# SCH__Atlas_2026-06-26.net
KiCad netlist of a schematic drawn in EasyEDA
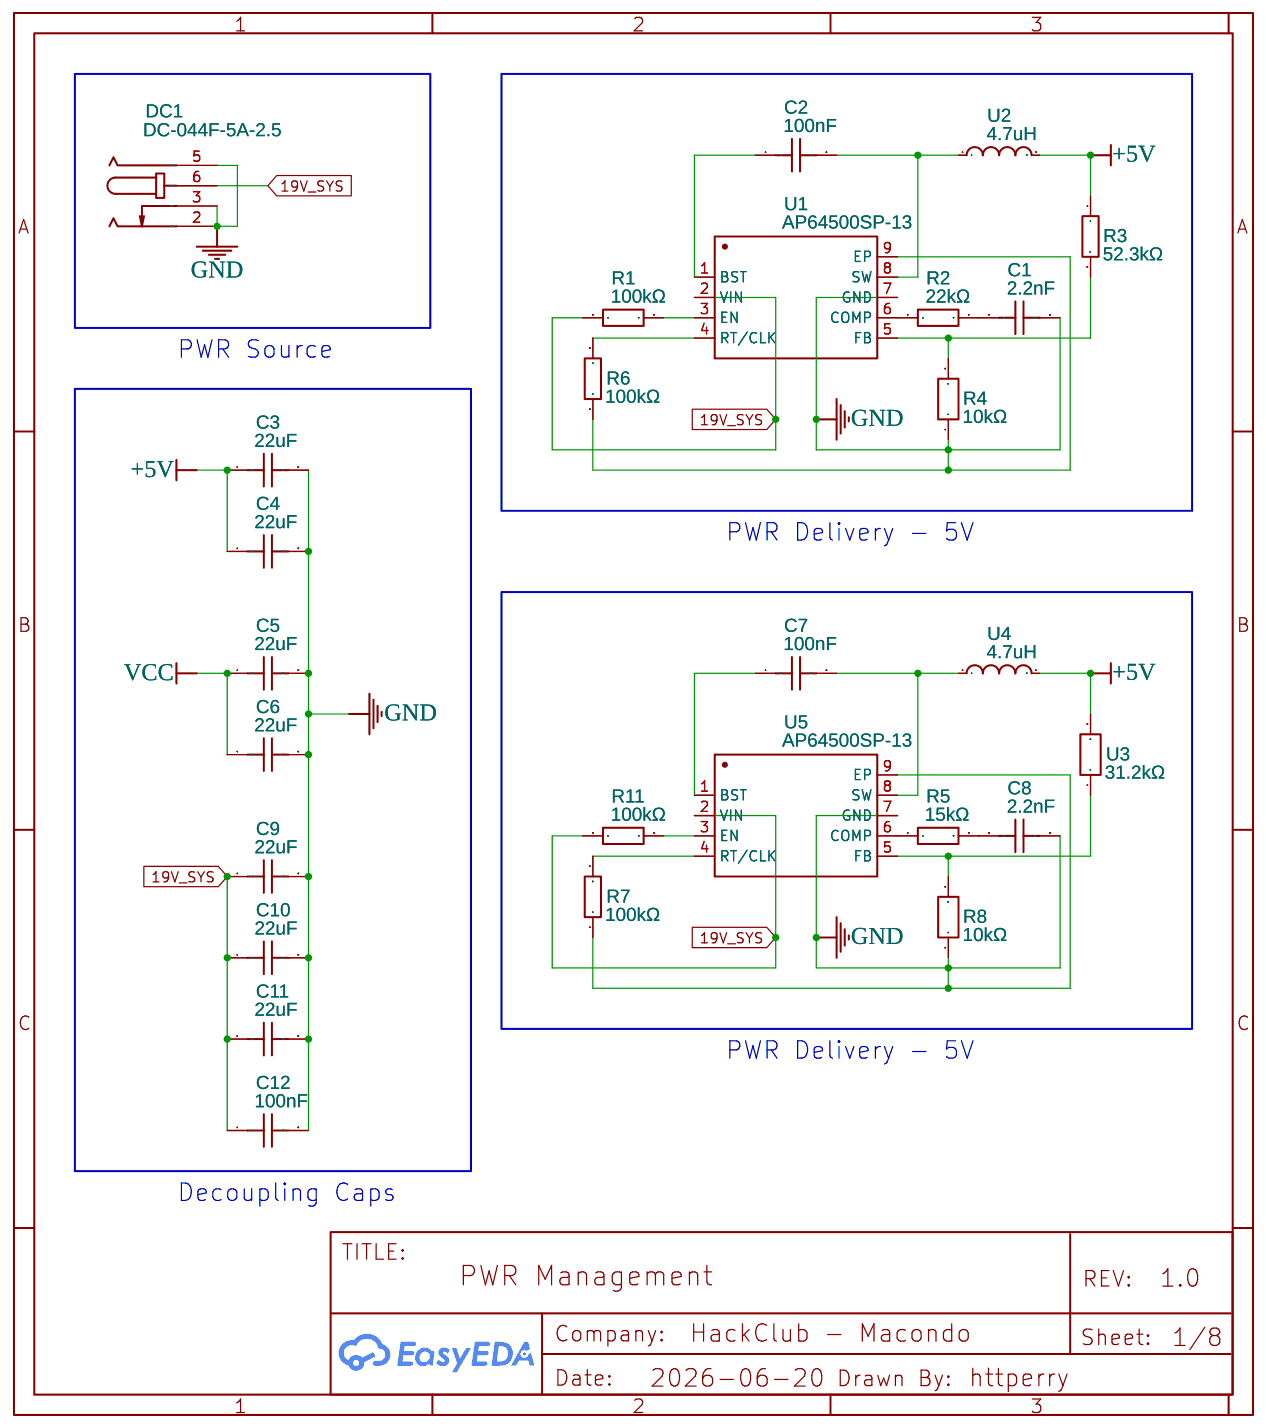
[diagram p0: PWR_Management]
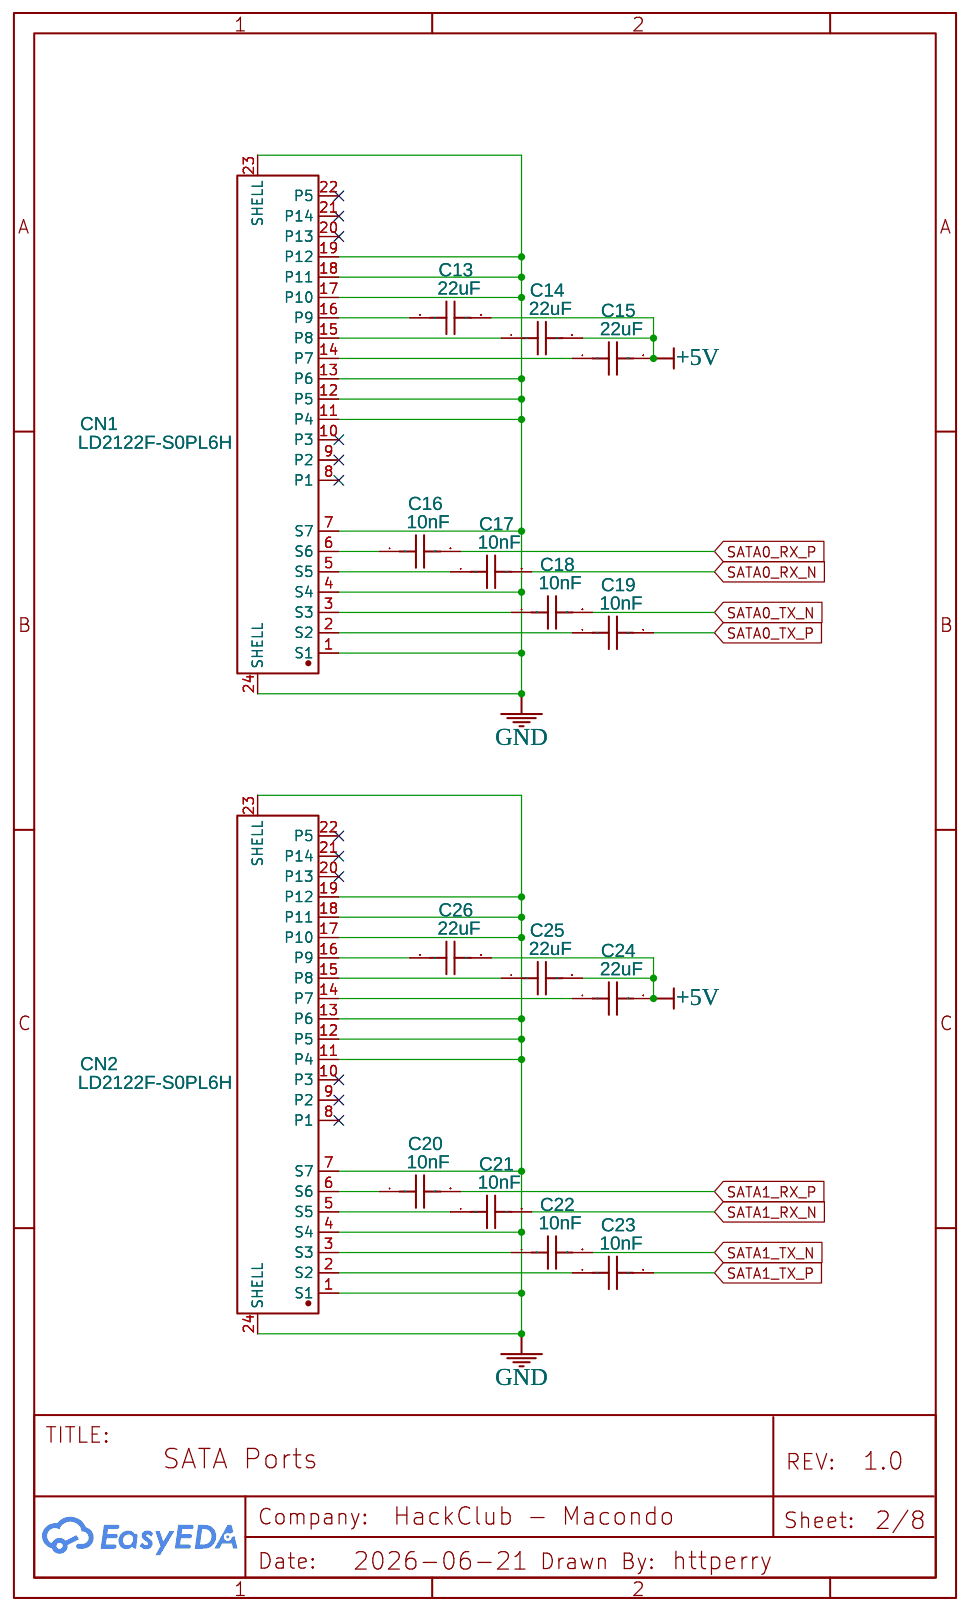
[diagram p1: SATA_Ports]
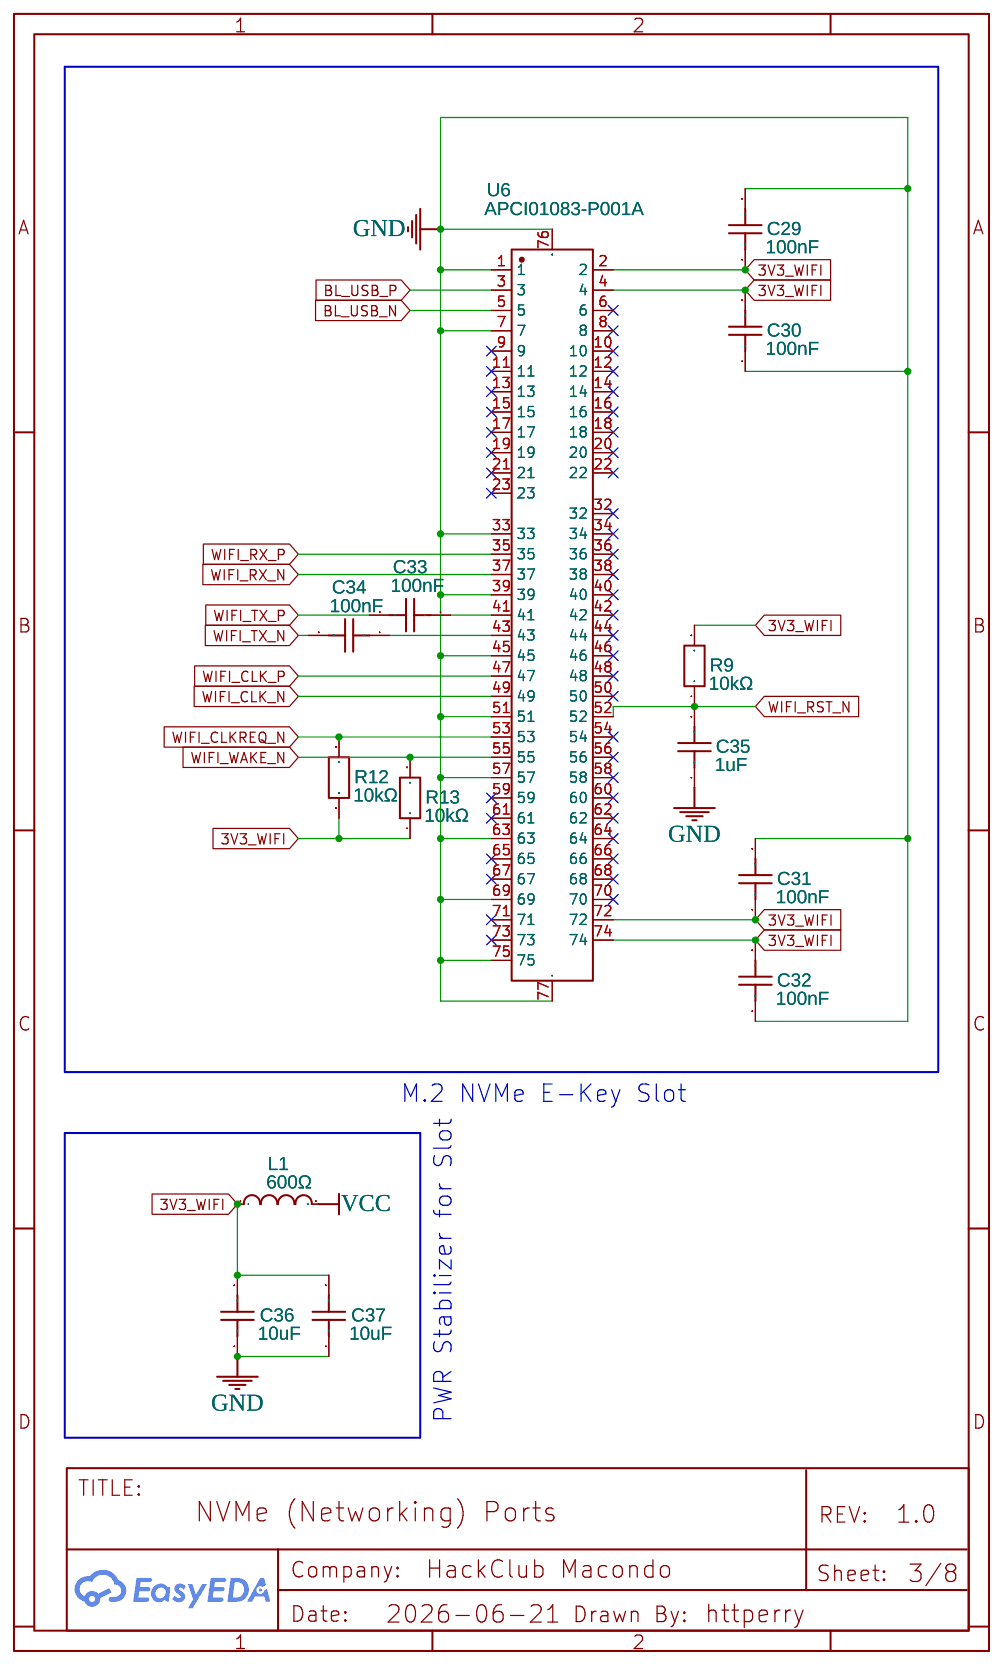
[diagram p2: NVMe_(Networking)_Ports]
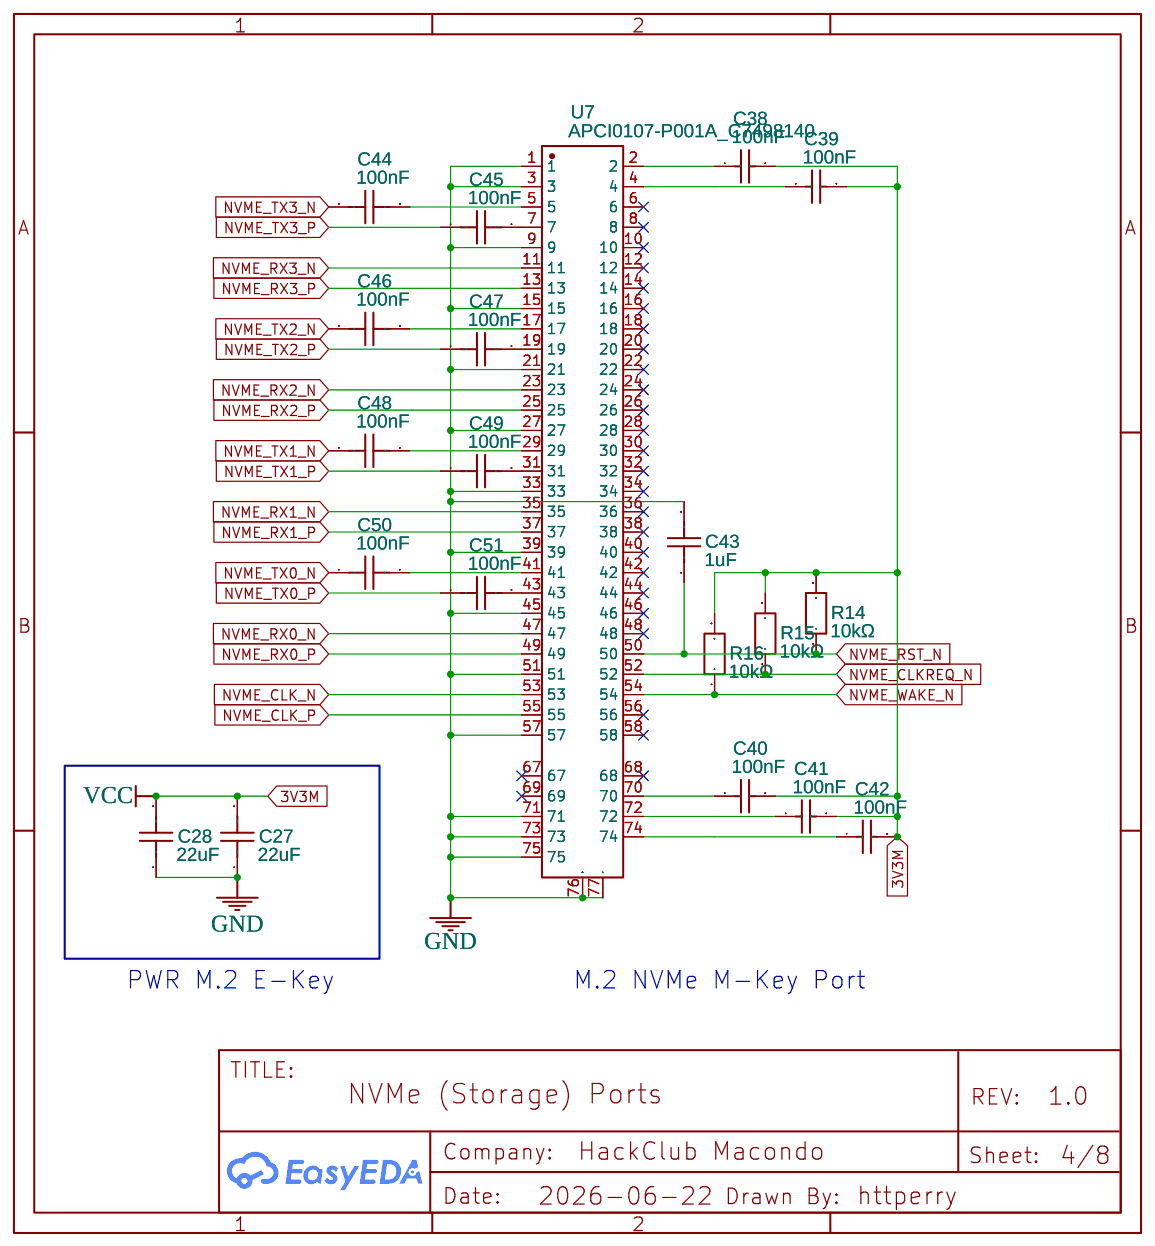
[diagram p3: NVMe_(Storage)_Ports]
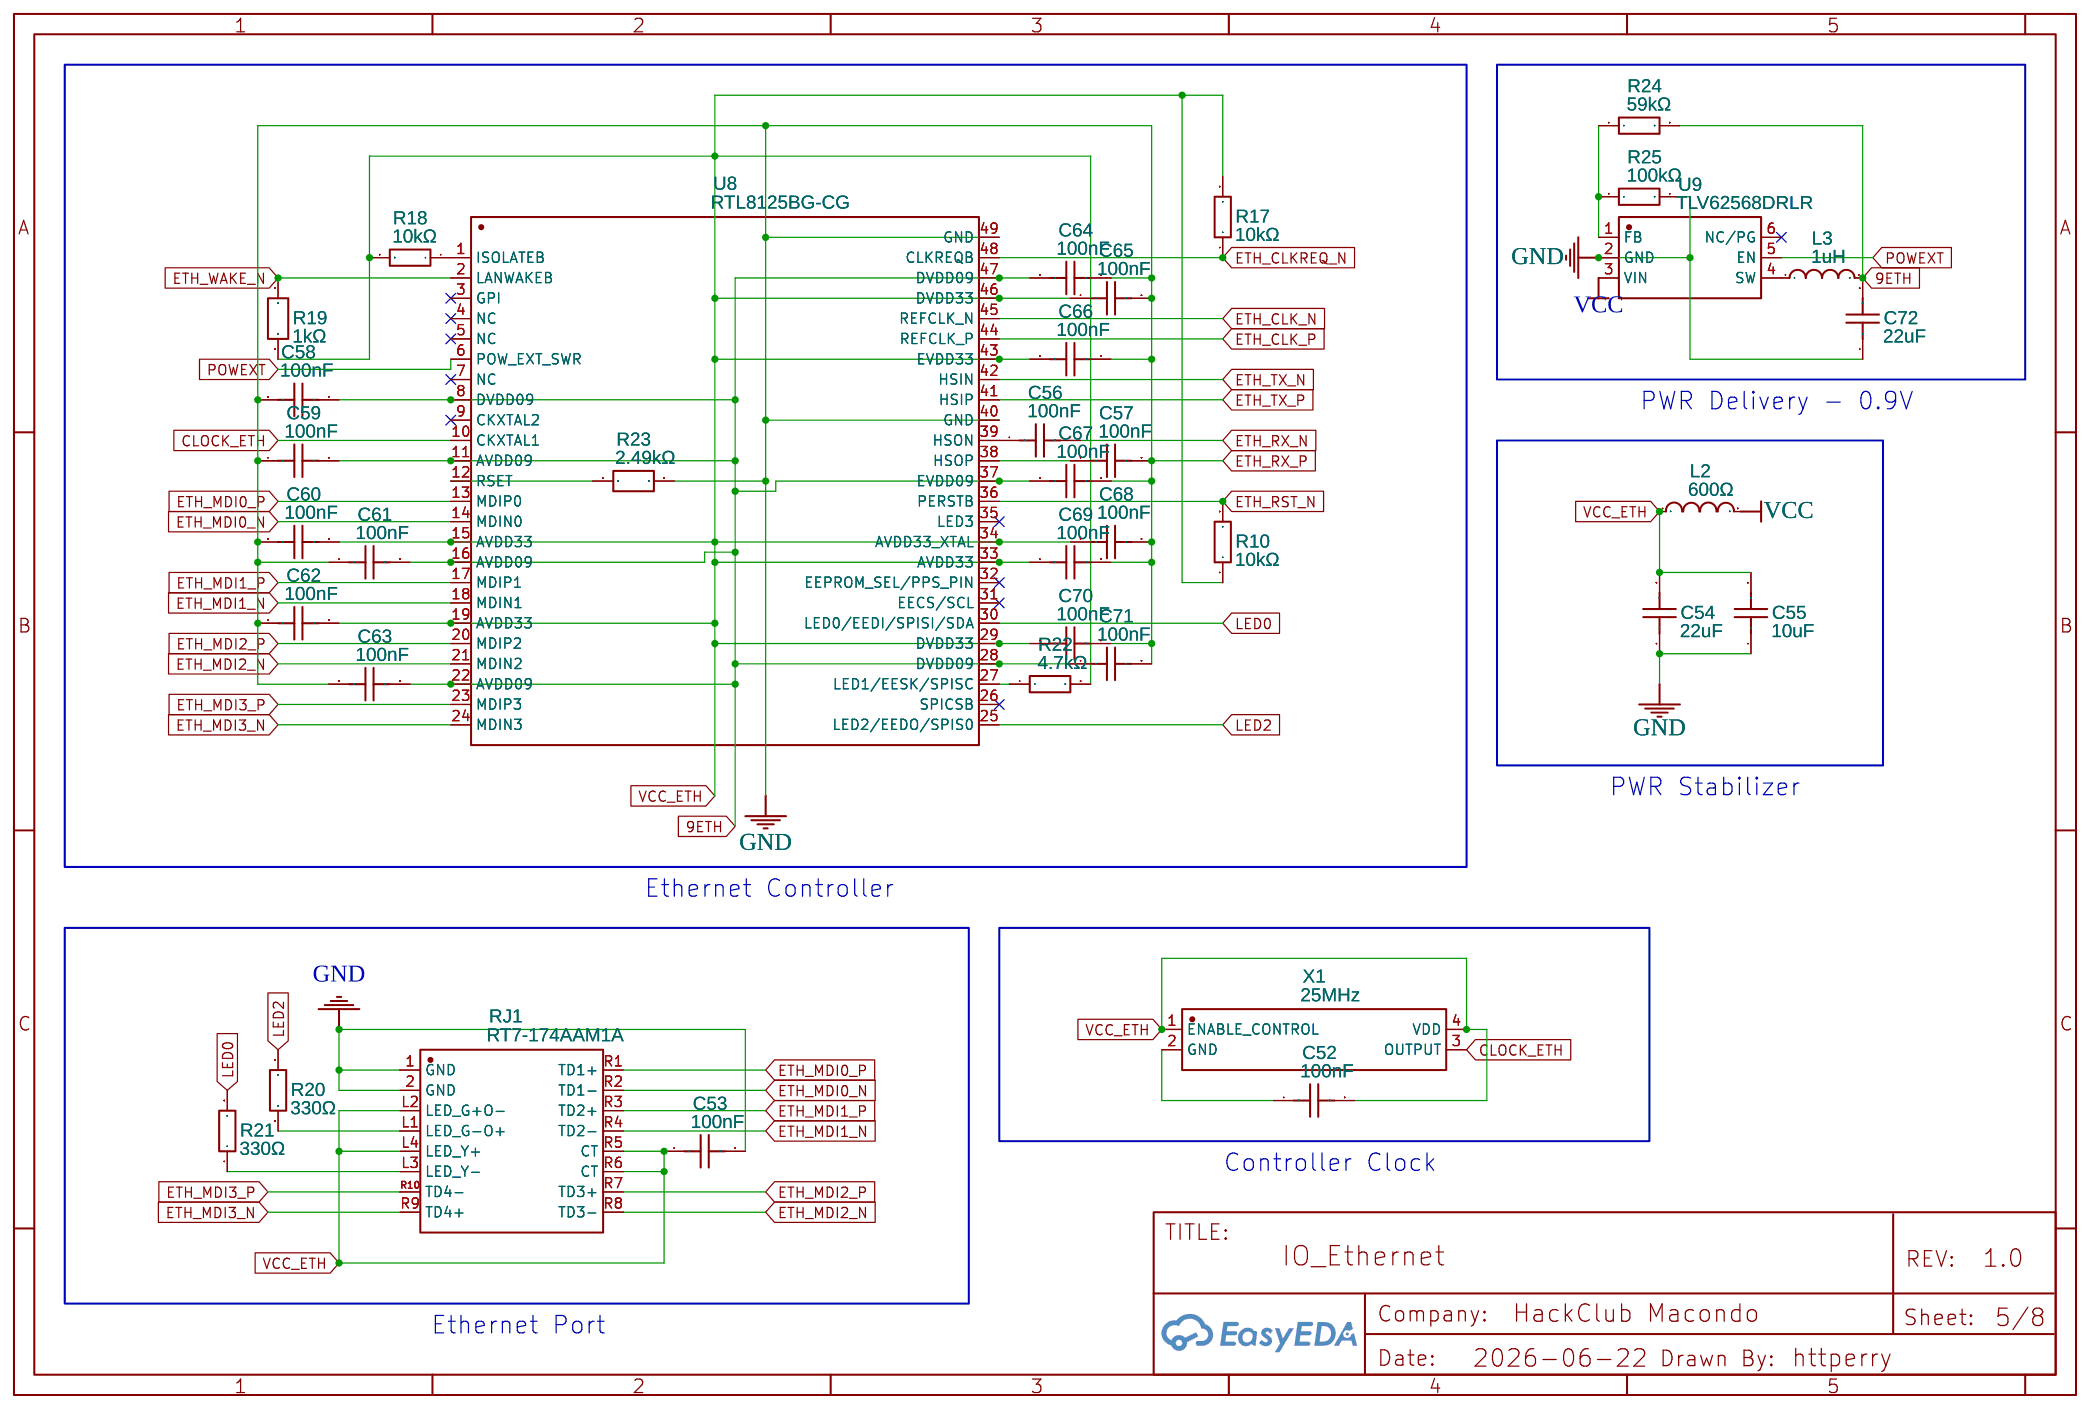
[diagram p4: IO_Ethernet]
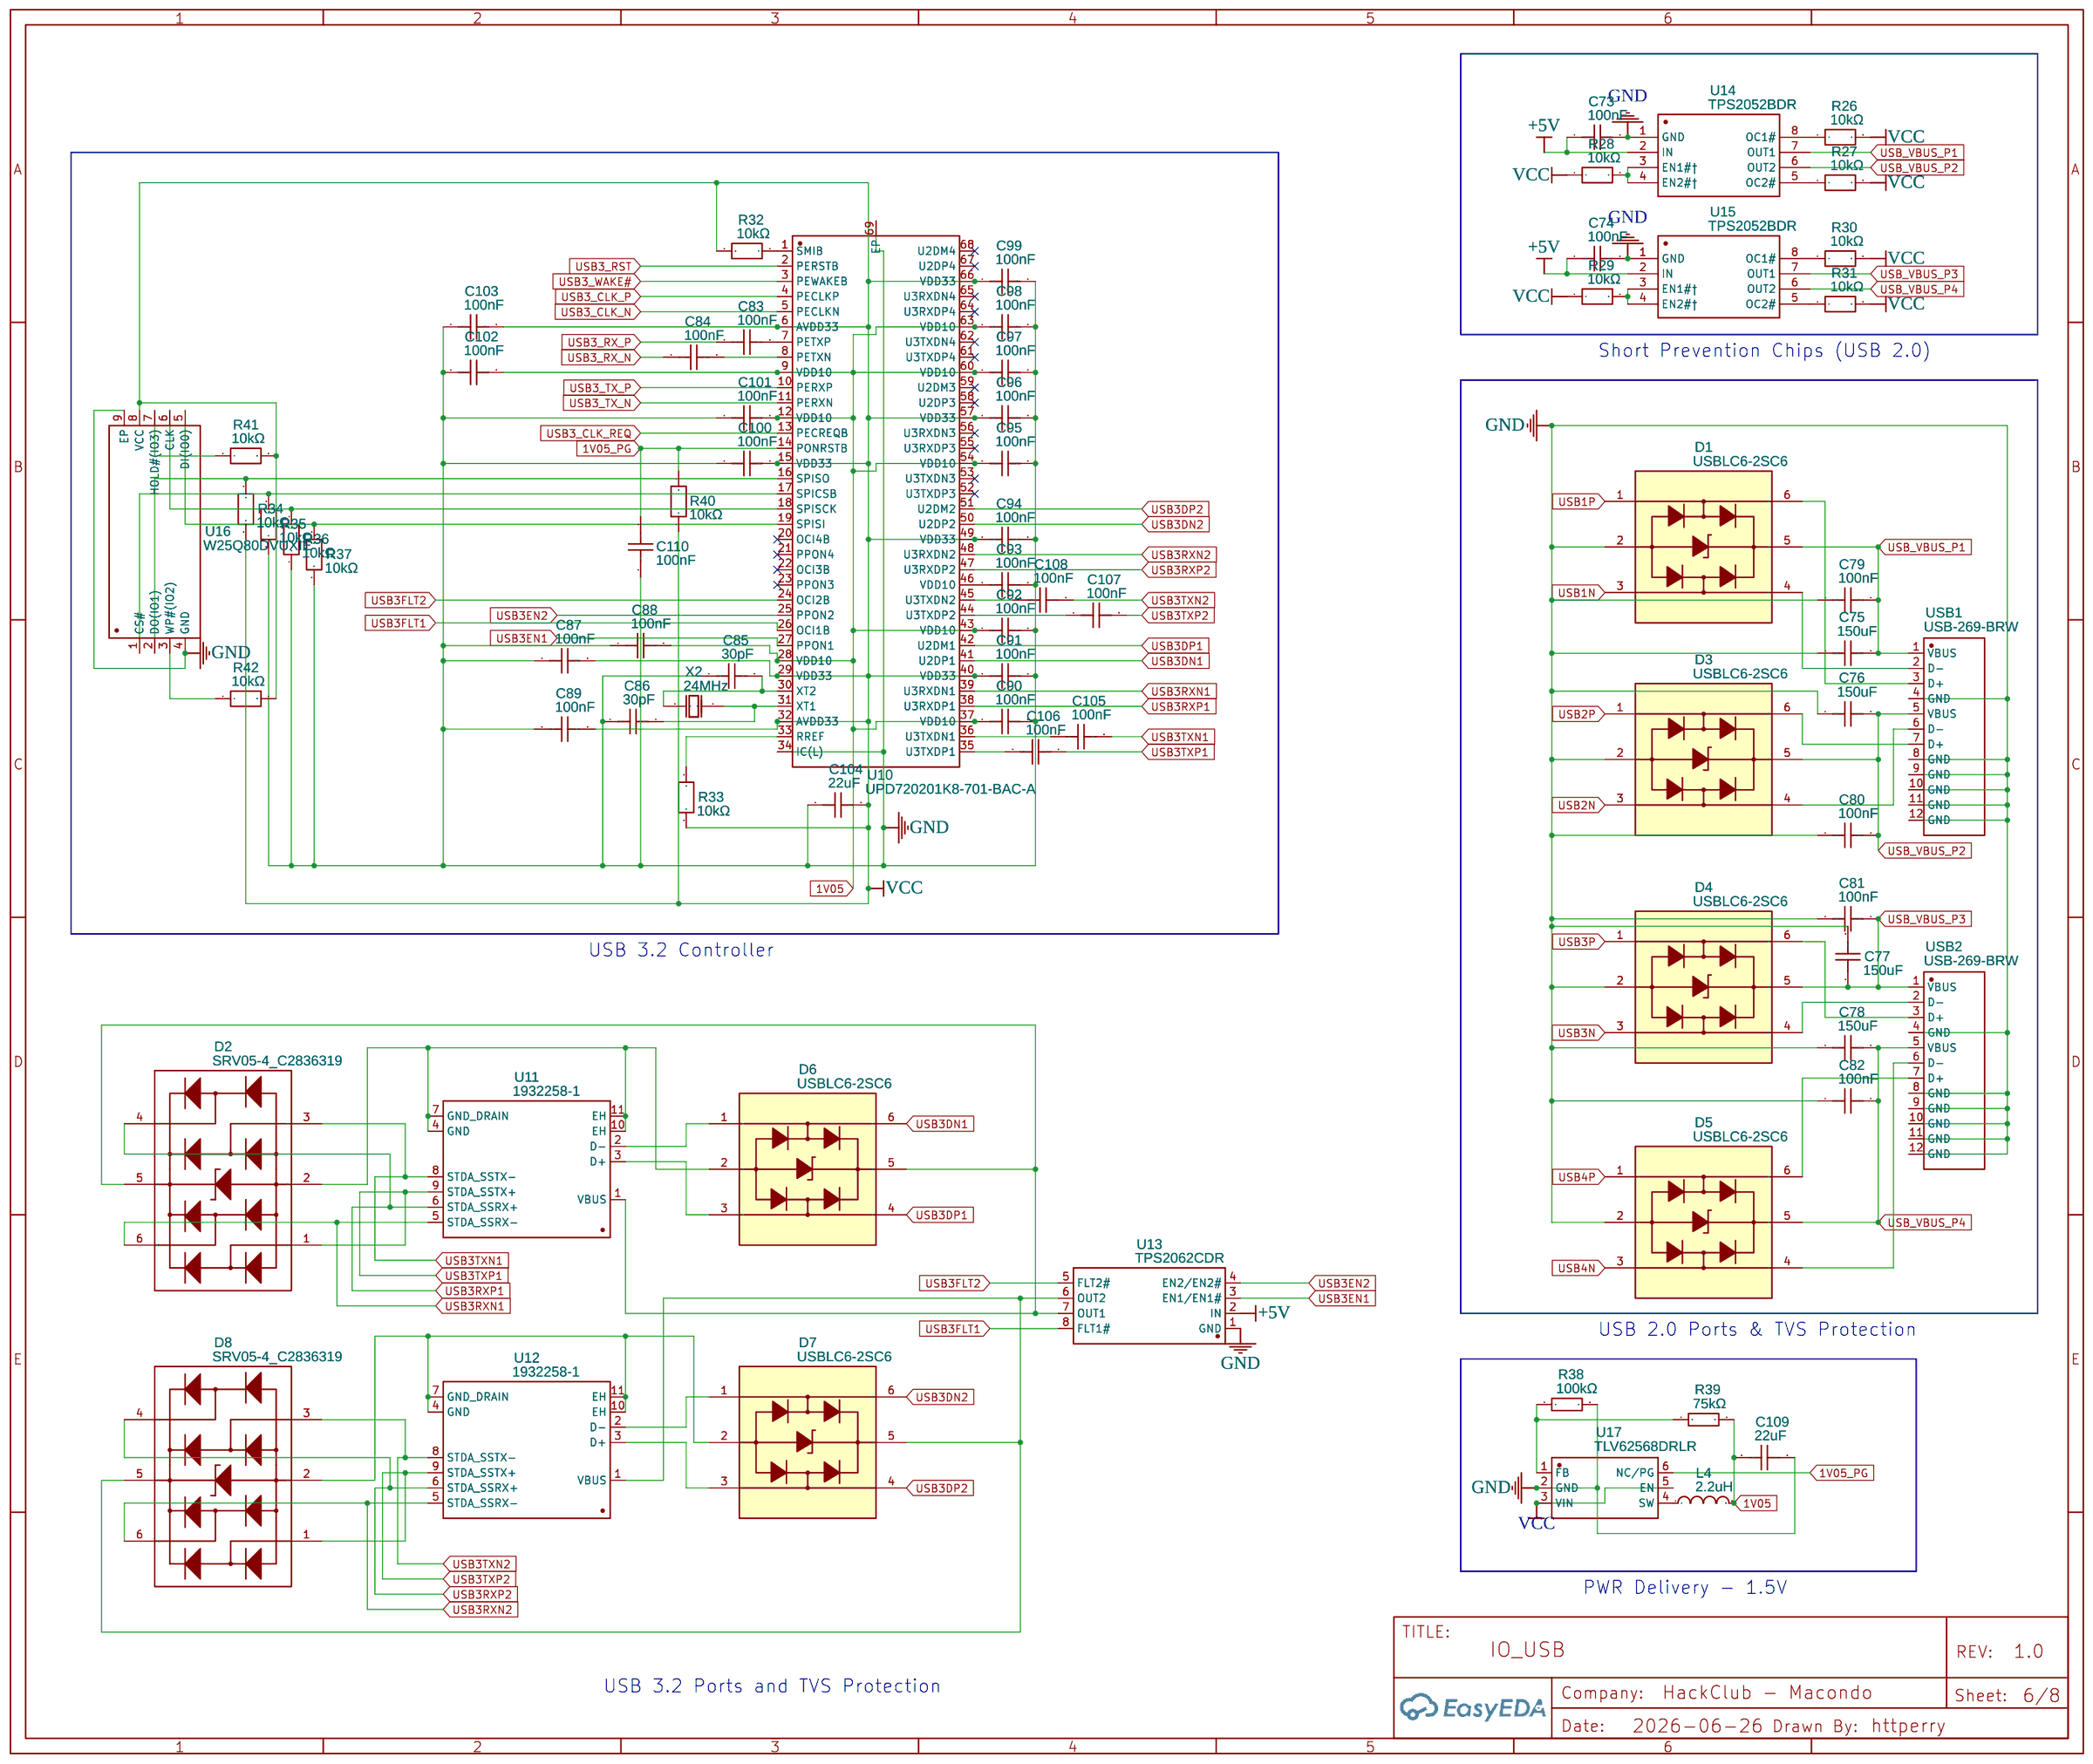
[diagram p5: IO_USB]

(export (version "E")
  (design (tool "Eeschema 10.0.6"))
  (components
    (comp (ref "C1")
      (value "2.2nF")
      (fields
        (field (name "Manufacturer Part") "FCC0603B222K500CT")
        (field (name "Manufacturer") "FOJAN(富捷)")
      )
      (libsource (lib "") (part "FCC0603B222K500CT"))
    )
    (comp (ref "C2")
      (value "100nF")
      (fields
        (field (name "Manufacturer Part") "GRM188R71H104KA93D")
        (field (name "Manufacturer") "muRata(村田)")
      )
      (libsource (lib "") (part "GRM188R71H104KA93D"))
    )
    (comp (ref "C3")
      (value "22uF")
      (fields
        (field (name "Manufacturer Part") "HGC0603R5226M160NTHJ")
        (field (name "Manufacturer") "Chinocera(华瓷)")
      )
      (libsource (lib "") (part "HGC0603R5226M160NTHJ"))
    )
    (comp (ref "C4")
      (value "22uF")
      (fields
        (field (name "Manufacturer Part") "HGC0603R5226M160NTHJ")
        (field (name "Manufacturer") "Chinocera(华瓷)")
      )
      (libsource (lib "") (part "HGC0603R5226M160NTHJ"))
    )
    (comp (ref "C5")
      (value "22uF")
      (fields
        (field (name "Manufacturer Part") "HGC0603R5226M160NTHJ")
        (field (name "Manufacturer") "Chinocera(华瓷)")
      )
      (libsource (lib "") (part "HGC0603R5226M160NTHJ"))
    )
    (comp (ref "C6")
      (value "22uF")
      (fields
        (field (name "Manufacturer Part") "HGC0603R5226M160NTHJ")
        (field (name "Manufacturer") "Chinocera(华瓷)")
      )
      (libsource (lib "") (part "HGC0603R5226M160NTHJ"))
    )
    (comp (ref "C7")
      (value "100nF")
      (fields
        (field (name "Manufacturer Part") "GRM188R71H104KA93D")
        (field (name "Manufacturer") "muRata(村田)")
      )
      (libsource (lib "") (part "GRM188R71H104KA93D"))
    )
    (comp (ref "C8")
      (value "2.2nF")
      (fields
        (field (name "Manufacturer Part") "FCC0603B222K500CT")
        (field (name "Manufacturer") "FOJAN(富捷)")
      )
      (libsource (lib "") (part "FCC0603B222K500CT"))
    )
    (comp (ref "C9")
      (value "22uF")
      (fields
        (field (name "Manufacturer Part") "KCM55QR71H226KH13K")
        (field (name "Manufacturer") "muRata(村田)")
      )
      (libsource (lib "") (part "KCM55QR71H226KH13K"))
    )
    (comp (ref "C10")
      (value "22uF")
      (fields
        (field (name "Manufacturer Part") "KCM55QR71H226KH13K")
        (field (name "Manufacturer") "muRata(村田)")
      )
      (libsource (lib "") (part "KCM55QR71H226KH13K"))
    )
    (comp (ref "C11")
      (value "22uF")
      (fields
        (field (name "Manufacturer Part") "KCM55QR71H226KH13K")
        (field (name "Manufacturer") "muRata(村田)")
      )
      (libsource (lib "") (part "KCM55QR71H226KH13K"))
    )
    (comp (ref "C12")
      (value "100nF")
      (fields
        (field (name "Manufacturer Part") "GRM188R71H104KA93D")
        (field (name "Manufacturer") "muRata(村田)")
      )
      (libsource (lib "") (part "GRM188R71H104KA93D"))
    )
    (comp (ref "DC1")
      (value "DC-044F-5A-2.5")
      (fields (field (name "Manufacturer") "XKB Connection(中国星坤)"))
      (libsource (lib "") (part "DC-044F-5A-2.5"))
    )
    (comp (ref "R1")
      (value "100kΩ")
      (fields (field (name "Manufacturer Part") "RS-03K1003FT") (field (name "Manufacturer") "FH(风华)"))
      (libsource (lib "") (part "RS-03K1003FT_C115320_1"))
    )
    (comp (ref "R2")
      (value "22kΩ")
      (fields (field (name "Manufacturer Part") "RS-03K2202FT") (field (name "Manufacturer") "FH(风华)"))
      (libsource (lib "") (part "RS-03K2202FT"))
    )
    (comp (ref "R3")
      (value "52.3kΩ")
      (fields (field (name "Manufacturer Part") "RS-03K5232FT") (field (name "Manufacturer") "FH(风华)"))
      (libsource (lib "") (part "RS-03K5232FT"))
    )
    (comp (ref "R4")
      (value "10kΩ")
      (fields (field (name "Manufacturer Part") "AR03BTS1002") (field (name "Manufacturer") "Viking(光颉)"))
      (libsource (lib "") (part "AR03BTS1002"))
    )
    (comp (ref "R5")
      (value "15kΩ")
      (fields (field (name "Manufacturer Part") "CR0603FA1502G") (field (name "Manufacturer") "LIZ(丽智电子)"))
      (libsource (lib "") (part "CR0603FA1502G"))
    )
    (comp (ref "R6")
      (value "100kΩ")
      (fields (field (name "Manufacturer Part") "RS-03K1003FT") (field (name "Manufacturer") "FH(风华)"))
      (libsource (lib "") (part "RS-03K1003FT_C115320"))
    )
    (comp (ref "R7")
      (value "100kΩ")
      (fields (field (name "Manufacturer Part") "RS-03K1003FT") (field (name "Manufacturer") "FH(风华)"))
      (libsource (lib "") (part "RS-03K1003FT_C115320"))
    )
    (comp (ref "R8")
      (value "10kΩ")
      (fields (field (name "Manufacturer Part") "AR03BTS1002") (field (name "Manufacturer") "Viking(光颉)"))
      (libsource (lib "") (part "AR03BTS1002"))
    )
    (comp (ref "R11")
      (value "100kΩ")
      (fields (field (name "Manufacturer Part") "RS-03K1003FT") (field (name "Manufacturer") "FH(风华)"))
      (libsource (lib "") (part "RS-03K1003FT_C115320_1"))
    )
    (comp (ref "U1")
      (value "AP64500SP-13")
      (fields (field (name "Manufacturer") "DIODES(美台)"))
      (libsource (lib "") (part "AP64500SP-13"))
    )
    (comp (ref "U2")
      (value "4.7uH")
      (fields (field (name "Manufacturer Part") "APH0630T4R7M") (field (name "Manufacturer") "APV(爱普微)"))
      (libsource (lib "") (part "APH0630T4R7M"))
    )
    (comp (ref "U3")
      (value "31.2kΩ")
      (fields (field (name "Manufacturer Part") "RT0603DRE0731K2L") (field (name "Manufacturer") "YAGEO(国巨)"))
      (libsource (lib "") (part "RT0603DRE0731K2L"))
    )
    (comp (ref "U4")
      (value "4.7uH")
      (fields (field (name "Manufacturer Part") "APH0630T4R7M") (field (name "Manufacturer") "APV(爱普微)"))
      (libsource (lib "") (part "APH0630T4R7M"))
    )
    (comp (ref "U5")
      (value "AP64500SP-13")
      (fields (field (name "Manufacturer") "DIODES(美台)"))
      (libsource (lib "") (part "AP64500SP-13"))
    )
    (comp (ref "C13")
      (value "22uF")
      (fields
        (field (name "Manufacturer Part") "HGC0603R5226M160NTHJ")
        (field (name "Manufacturer") "Chinocera(华瓷)")
      )
      (libsource (lib "") (part "HGC0603R5226M160NTHJ"))
    )
    (comp (ref "C14")
      (value "22uF")
      (fields
        (field (name "Manufacturer Part") "HGC0603R5226M160NTHJ")
        (field (name "Manufacturer") "Chinocera(华瓷)")
      )
      (libsource (lib "") (part "HGC0603R5226M160NTHJ"))
    )
    (comp (ref "C15")
      (value "22uF")
      (fields
        (field (name "Manufacturer Part") "HGC0603R5226M160NTHJ")
        (field (name "Manufacturer") "Chinocera(华瓷)")
      )
      (libsource (lib "") (part "HGC0603R5226M160NTHJ"))
    )
    (comp (ref "C16")
      (value "10nF")
      (fields
        (field (name "Manufacturer Part") "FCC0402B103K500AT")
        (field (name "Manufacturer") "FOJAN(富捷)")
      )
      (libsource (lib "") (part "FCC0402B103K500AT"))
    )
    (comp (ref "C17")
      (value "10nF")
      (fields
        (field (name "Manufacturer Part") "FCC0402B103K500AT")
        (field (name "Manufacturer") "FOJAN(富捷)")
      )
      (libsource (lib "") (part "FCC0402B103K500AT"))
    )
    (comp (ref "C18")
      (value "10nF")
      (fields
        (field (name "Manufacturer Part") "FCC0402B103K500AT")
        (field (name "Manufacturer") "FOJAN(富捷)")
      )
      (libsource (lib "") (part "FCC0402B103K500AT"))
    )
    (comp (ref "C19")
      (value "10nF")
      (fields
        (field (name "Manufacturer Part") "FCC0402B103K500AT")
        (field (name "Manufacturer") "FOJAN(富捷)")
      )
      (libsource (lib "") (part "FCC0402B103K500AT"))
    )
    (comp (ref "C20")
      (value "10nF")
      (fields
        (field (name "Manufacturer Part") "FCC0402B103K500AT")
        (field (name "Manufacturer") "FOJAN(富捷)")
      )
      (libsource (lib "") (part "FCC0402B103K500AT"))
    )
    (comp (ref "C21")
      (value "10nF")
      (fields
        (field (name "Manufacturer Part") "FCC0402B103K500AT")
        (field (name "Manufacturer") "FOJAN(富捷)")
      )
      (libsource (lib "") (part "FCC0402B103K500AT"))
    )
    (comp (ref "C22")
      (value "10nF")
      (fields
        (field (name "Manufacturer Part") "FCC0402B103K500AT")
        (field (name "Manufacturer") "FOJAN(富捷)")
      )
      (libsource (lib "") (part "FCC0402B103K500AT"))
    )
    (comp (ref "C23")
      (value "10nF")
      (fields
        (field (name "Manufacturer Part") "FCC0402B103K500AT")
        (field (name "Manufacturer") "FOJAN(富捷)")
      )
      (libsource (lib "") (part "FCC0402B103K500AT"))
    )
    (comp (ref "C24")
      (value "22uF")
      (fields
        (field (name "Manufacturer Part") "HGC0603R5226M160NTHJ")
        (field (name "Manufacturer") "Chinocera(华瓷)")
      )
      (libsource (lib "") (part "HGC0603R5226M160NTHJ"))
    )
    (comp (ref "C25")
      (value "22uF")
      (fields
        (field (name "Manufacturer Part") "HGC0603R5226M160NTHJ")
        (field (name "Manufacturer") "Chinocera(华瓷)")
      )
      (libsource (lib "") (part "HGC0603R5226M160NTHJ"))
    )
    (comp (ref "C26")
      (value "22uF")
      (fields
        (field (name "Manufacturer Part") "HGC0603R5226M160NTHJ")
        (field (name "Manufacturer") "Chinocera(华瓷)")
      )
      (libsource (lib "") (part "HGC0603R5226M160NTHJ"))
    )
    (comp (ref "CN1")
      (value "LD2122F-S0PL6H")
      (fields (field (name "Manufacturer") "FOXCONN(富士康)"))
      (libsource (lib "") (part "LD2122F-S0PL6H"))
    )
    (comp (ref "CN2")
      (value "LD2122F-S0PL6H")
      (fields (field (name "Manufacturer") "FOXCONN(富士康)"))
      (libsource (lib "") (part "LD2122F-S0PL6H"))
    )
    (comp (ref "C29")
      (value "100nF")
      (fields
        (field (name "Manufacturer Part") "CC0402KRX5R6BB104")
        (field (name "Manufacturer") "YAGEO(国巨)")
      )
      (libsource (lib "") (part "CC0402KRX5R6BB104_1"))
    )
    (comp (ref "C30")
      (value "100nF")
      (fields
        (field (name "Manufacturer Part") "CC0402KRX5R6BB104")
        (field (name "Manufacturer") "YAGEO(国巨)")
      )
      (libsource (lib "") (part "CC0402KRX5R6BB104_1"))
    )
    (comp (ref "C31")
      (value "100nF")
      (fields
        (field (name "Manufacturer Part") "CC0402KRX5R6BB104")
        (field (name "Manufacturer") "YAGEO(国巨)")
      )
      (libsource (lib "") (part "CC0402KRX5R6BB104_1"))
    )
    (comp (ref "C32")
      (value "100nF")
      (fields
        (field (name "Manufacturer Part") "CC0402KRX5R6BB104")
        (field (name "Manufacturer") "YAGEO(国巨)")
      )
      (libsource (lib "") (part "CC0402KRX5R6BB104_1"))
    )
    (comp (ref "C33")
      (value "100nF")
      (fields
        (field (name "Manufacturer Part") "CC0402KRX5R6BB104")
        (field (name "Manufacturer") "YAGEO(国巨)")
      )
      (libsource (lib "") (part "CC0402KRX5R6BB104"))
    )
    (comp (ref "C34")
      (value "100nF")
      (fields
        (field (name "Manufacturer Part") "CC0402KRX5R6BB104")
        (field (name "Manufacturer") "YAGEO(国巨)")
      )
      (libsource (lib "") (part "CC0402KRX5R6BB104"))
    )
    (comp (ref "C35")
      (value "1uF")
      (fields
        (field (name "Manufacturer Part") "TCC0402X5R105K160AT")
        (field (name "Manufacturer") "CCTC(三环)")
      )
      (libsource (lib "") (part "TCC0402X5R105K160AT"))
    )
    (comp (ref "C36")
      (value "10uF")
      (fields
        (field (name "Manufacturer Part") "CGA0805X5R106K500MT")
        (field (name "Manufacturer") "HRE(芯声)")
      )
      (libsource (lib "") (part "CGA0805X5R106K500MT"))
    )
    (comp (ref "C37")
      (value "10uF")
      (fields
        (field (name "Manufacturer Part") "CGA0805X5R106K500MT")
        (field (name "Manufacturer") "HRE(芯声)")
      )
      (libsource (lib "") (part "CGA0805X5R106K500MT"))
    )
    (comp (ref "L1")
      (value "600Ω")
      (fields (field (name "Manufacturer Part") "MPZ2012S601AT000") (field (name "Manufacturer") "TDK"))
      (libsource (lib "") (part "MPZ2012S601AT000"))
    )
    (comp (ref "R9")
      (value "10kΩ")
      (fields (field (name "Manufacturer Part") "FRC0402F1002TS") (field (name "Manufacturer") "FOJAN(富捷)"))
      (libsource (lib "") (part "FRC0402F1002TS"))
    )
    (comp (ref "R12")
      (value "10kΩ")
      (fields (field (name "Manufacturer Part") "FRC0402F1002TS") (field (name "Manufacturer") "FOJAN(富捷)"))
      (libsource (lib "") (part "FRC0402F1002TS"))
    )
    (comp (ref "R13")
      (value "10kΩ")
      (fields (field (name "Manufacturer Part") "FRC0402F1002TS") (field (name "Manufacturer") "FOJAN(富捷)"))
      (libsource (lib "") (part "FRC0402F1002TS"))
    )
    (comp (ref "U6")
      (value "APCI01083-P001A")
      (fields (field (name "Manufacturer") "LX(连欣科技)"))
      (libsource (lib "") (part "APCI01083-P001A"))
    )
    (comp (ref "C27")
      (value "22uF")
      (fields
        (field (name "Manufacturer Part") "CL21A226MAYNNNE")
        (field (name "Manufacturer") "SAMSUNG(三星)")
      )
      (libsource (lib "") (part "CL21A226MAYNNNE"))
    )
    (comp (ref "C28")
      (value "22uF")
      (fields
        (field (name "Manufacturer Part") "CL21A226MAYNNNE")
        (field (name "Manufacturer") "SAMSUNG(三星)")
      )
      (libsource (lib "") (part "CL21A226MAYNNNE"))
    )
    (comp (ref "C38")
      (value "100nF")
      (fields
        (field (name "Manufacturer Part") "CC0402KRX5R8BB104")
        (field (name "Manufacturer") "YAGEO(国巨)")
      )
      (libsource (lib "") (part "CC0402KRX5R8BB104"))
    )
    (comp (ref "C39")
      (value "100nF")
      (fields
        (field (name "Manufacturer Part") "CC0402KRX5R8BB104")
        (field (name "Manufacturer") "YAGEO(国巨)")
      )
      (libsource (lib "") (part "CC0402KRX5R8BB104"))
    )
    (comp (ref "C40")
      (value "100nF")
      (fields
        (field (name "Manufacturer Part") "CC0402KRX5R8BB104")
        (field (name "Manufacturer") "YAGEO(国巨)")
      )
      (libsource (lib "") (part "CC0402KRX5R8BB104"))
    )
    (comp (ref "C41")
      (value "100nF")
      (fields
        (field (name "Manufacturer Part") "CC0402KRX5R8BB104")
        (field (name "Manufacturer") "YAGEO(国巨)")
      )
      (libsource (lib "") (part "CC0402KRX5R8BB104"))
    )
    (comp (ref "C42")
      (value "100nF")
      (fields
        (field (name "Manufacturer Part") "CC0402KRX5R8BB104")
        (field (name "Manufacturer") "YAGEO(国巨)")
      )
      (libsource (lib "") (part "CC0402KRX5R8BB104"))
    )
    (comp (ref "C43")
      (value "1uF")
      (fields
        (field (name "Manufacturer Part") "HGC0402R5105K500NTEJ")
        (field (name "Manufacturer") "Chinocera(华瓷)")
      )
      (libsource (lib "") (part "HGC0402R5105K500NTEJ"))
    )
    (comp (ref "C44")
      (value "100nF")
      (fields
        (field (name "Manufacturer Part") "GRM155R71H104KE14J")
        (field (name "Manufacturer") "muRata(村田)")
      )
      (libsource (lib "") (part "GRM155R71H104KE14J"))
    )
    (comp (ref "C45")
      (value "100nF")
      (fields
        (field (name "Manufacturer Part") "GRM155R71H104KE14J")
        (field (name "Manufacturer") "muRata(村田)")
      )
      (libsource (lib "") (part "GRM155R71H104KE14J"))
    )
    (comp (ref "C46")
      (value "100nF")
      (fields
        (field (name "Manufacturer Part") "GRM155R71H104KE14J")
        (field (name "Manufacturer") "muRata(村田)")
      )
      (libsource (lib "") (part "GRM155R71H104KE14J"))
    )
    (comp (ref "C47")
      (value "100nF")
      (fields
        (field (name "Manufacturer Part") "GRM155R71H104KE14J")
        (field (name "Manufacturer") "muRata(村田)")
      )
      (libsource (lib "") (part "GRM155R71H104KE14J"))
    )
    (comp (ref "C48")
      (value "100nF")
      (fields
        (field (name "Manufacturer Part") "GRM155R71H104KE14J")
        (field (name "Manufacturer") "muRata(村田)")
      )
      (libsource (lib "") (part "GRM155R71H104KE14J"))
    )
    (comp (ref "C49")
      (value "100nF")
      (fields
        (field (name "Manufacturer Part") "GRM155R71H104KE14J")
        (field (name "Manufacturer") "muRata(村田)")
      )
      (libsource (lib "") (part "GRM155R71H104KE14J"))
    )
    (comp (ref "C50")
      (value "100nF")
      (fields
        (field (name "Manufacturer Part") "GRM155R71H104KE14J")
        (field (name "Manufacturer") "muRata(村田)")
      )
      (libsource (lib "") (part "GRM155R71H104KE14J"))
    )
    (comp (ref "C51")
      (value "100nF")
      (fields
        (field (name "Manufacturer Part") "GRM155R71H104KE14J")
        (field (name "Manufacturer") "muRata(村田)")
      )
      (libsource (lib "") (part "GRM155R71H104KE14J"))
    )
    (comp (ref "R14")
      (value "10kΩ")
      (fields (field (name "Manufacturer Part") "FRC0402F1002TS") (field (name "Manufacturer") "FOJAN(富捷)"))
      (libsource (lib "") (part "FRC0402F1002TS"))
    )
    (comp (ref "R15")
      (value "10kΩ")
      (fields (field (name "Manufacturer Part") "FRC0402F1002TS") (field (name "Manufacturer") "FOJAN(富捷)"))
      (libsource (lib "") (part "FRC0402F1002TS"))
    )
    (comp (ref "R16")
      (value "10kΩ")
      (fields (field (name "Manufacturer Part") "FRC0402F1002TS") (field (name "Manufacturer") "FOJAN(富捷)"))
      (libsource (lib "") (part "FRC0402F1002TS"))
    )
    (comp (ref "U7")
      (value "APCI0107-P001A_C7498140")
      (fields (field (name "Manufacturer Part") "APCI0107-P001A") (field (name "Manufacturer") "LX(连欣科技)"))
      (libsource (lib "") (part "APCI0107-P001A_C7498140"))
    )
    (comp (ref "C52")
      (value "100nF")
      (fields
        (field (name "Manufacturer Part") "GRM155R71H104KE14J")
        (field (name "Manufacturer") "muRata(村田)")
      )
      (libsource (lib "") (part "GRM155R71H104KE14J"))
    )
    (comp (ref "C53")
      (value "100nF")
      (fields
        (field (name "Manufacturer Part") "GRM155R71H104KE14J")
        (field (name "Manufacturer") "muRata(村田)")
      )
      (libsource (lib "") (part "GRM155R71H104KE14J"))
    )
    (comp (ref "C54")
      (value "22uF")
      (fields
        (field (name "Manufacturer Part") "GRT21BR61E226ME13L")
        (field (name "Manufacturer") "muRata(村田)")
      )
      (libsource (lib "") (part "GRT21BR61E226ME13L"))
    )
    (comp (ref "C55")
      (value "10uF")
      (fields
        (field (name "Manufacturer Part") "TCC0805X5R106K250FT")
        (field (name "Manufacturer") "CCTC(三环)")
      )
      (libsource (lib "") (part "TCC0805X5R106K250FT"))
    )
    (comp (ref "C56")
      (value "100nF")
      (fields
        (field (name "Manufacturer Part") "GRM155R71H104KE14J")
        (field (name "Manufacturer") "muRata(村田)")
      )
      (libsource (lib "") (part "GRM155R71H104KE14J"))
    )
    (comp (ref "C57")
      (value "100nF")
      (fields
        (field (name "Manufacturer Part") "GRM155R71H104KE14J")
        (field (name "Manufacturer") "muRata(村田)")
      )
      (libsource (lib "") (part "GRM155R71H104KE14J"))
    )
    (comp (ref "C58")
      (value "100nF")
      (fields
        (field (name "Manufacturer Part") "GRM155R71H104KE14J")
        (field (name "Manufacturer") "muRata(村田)")
      )
      (libsource (lib "") (part "GRM155R71H104KE14J_1"))
    )
    (comp (ref "C59")
      (value "100nF")
      (fields
        (field (name "Manufacturer Part") "GRM155R71H104KE14J")
        (field (name "Manufacturer") "muRata(村田)")
      )
      (libsource (lib "") (part "GRM155R71H104KE14J"))
    )
    (comp (ref "C60")
      (value "100nF")
      (fields
        (field (name "Manufacturer Part") "GRM155R71H104KE14J")
        (field (name "Manufacturer") "muRata(村田)")
      )
      (libsource (lib "") (part "GRM155R71H104KE14J"))
    )
    (comp (ref "C61")
      (value "100nF")
      (fields
        (field (name "Manufacturer Part") "GRM155R71H104KE14J")
        (field (name "Manufacturer") "muRata(村田)")
      )
      (libsource (lib "") (part "GRM155R71H104KE14J"))
    )
    (comp (ref "C62")
      (value "100nF")
      (fields
        (field (name "Manufacturer Part") "GRM155R71H104KE14J")
        (field (name "Manufacturer") "muRata(村田)")
      )
      (libsource (lib "") (part "GRM155R71H104KE14J"))
    )
    (comp (ref "C63")
      (value "100nF")
      (fields
        (field (name "Manufacturer Part") "GRM155R71H104KE14J")
        (field (name "Manufacturer") "muRata(村田)")
      )
      (libsource (lib "") (part "GRM155R71H104KE14J"))
    )
    (comp (ref "C64")
      (value "100nF")
      (fields
        (field (name "Manufacturer Part") "GRM155R71H104KE14J")
        (field (name "Manufacturer") "muRata(村田)")
      )
      (libsource (lib "") (part "GRM155R71H104KE14J"))
    )
    (comp (ref "C65")
      (value "100nF")
      (fields
        (field (name "Manufacturer Part") "GRM155R71H104KE14J")
        (field (name "Manufacturer") "muRata(村田)")
      )
      (libsource (lib "") (part "GRM155R71H104KE14J"))
    )
    (comp (ref "C66")
      (value "100nF")
      (fields
        (field (name "Manufacturer Part") "GRM155R71H104KE14J")
        (field (name "Manufacturer") "muRata(村田)")
      )
      (libsource (lib "") (part "GRM155R71H104KE14J"))
    )
    (comp (ref "C67")
      (value "100nF")
      (fields
        (field (name "Manufacturer Part") "GRM155R71H104KE14J")
        (field (name "Manufacturer") "muRata(村田)")
      )
      (libsource (lib "") (part "GRM155R71H104KE14J"))
    )
    (comp (ref "C68")
      (value "100nF")
      (fields
        (field (name "Manufacturer Part") "GRM155R71H104KE14J")
        (field (name "Manufacturer") "muRata(村田)")
      )
      (libsource (lib "") (part "GRM155R71H104KE14J"))
    )
    (comp (ref "C69")
      (value "100nF")
      (fields
        (field (name "Manufacturer Part") "GRM155R71H104KE14J")
        (field (name "Manufacturer") "muRata(村田)")
      )
      (libsource (lib "") (part "GRM155R71H104KE14J"))
    )
    (comp (ref "C70")
      (value "100nF")
      (fields
        (field (name "Manufacturer Part") "GRM155R71H104KE14J")
        (field (name "Manufacturer") "muRata(村田)")
      )
      (libsource (lib "") (part "GRM155R71H104KE14J"))
    )
    (comp (ref "C71")
      (value "100nF")
      (fields
        (field (name "Manufacturer Part") "GRM155R71H104KE14J")
        (field (name "Manufacturer") "muRata(村田)")
      )
      (libsource (lib "") (part "GRM155R71H104KE14J"))
    )
    (comp (ref "C72")
      (value "22uF")
      (fields
        (field (name "Manufacturer Part") "GRT21BR61E226ME13L")
        (field (name "Manufacturer") "muRata(村田)")
      )
      (libsource (lib "") (part "GRT21BR61E226ME13L"))
    )
    (comp (ref "L2")
      (value "600Ω")
      (fields (field (name "Manufacturer Part") "MPZ2012S601AT000") (field (name "Manufacturer") "TDK"))
      (libsource (lib "") (part "MPZ2012S601AT000"))
    )
    (comp (ref "L3")
      (value "1uH")
      (fields (field (name "Manufacturer Part") "XRIM201612S1R0MBCA") (field (name "Manufacturer") "XR(祥如)"))
      (libsource (lib "") (part "XRIM201612S1R0MBCA"))
    )
    (comp (ref "R10")
      (value "10kΩ")
      (fields (field (name "Manufacturer Part") "ERA2AEB103X") (field (name "Manufacturer") "PANASONIC(松下)"))
      (libsource (lib "") (part "ERA2AEB103X"))
    )
    (comp (ref "R17")
      (value "10kΩ")
      (fields (field (name "Manufacturer Part") "ERA2AEB103X") (field (name "Manufacturer") "PANASONIC(松下)"))
      (libsource (lib "") (part "ERA2AEB103X"))
    )
    (comp (ref "R18")
      (value "10kΩ")
      (fields (field (name "Manufacturer Part") "ERA2AEB103X") (field (name "Manufacturer") "PANASONIC(松下)"))
      (libsource (lib "") (part "ERA2AEB103X_1"))
    )
    (comp (ref "R19")
      (value "1kΩ")
      (fields (field (name "Manufacturer Part") "RT0402BRD071KL") (field (name "Manufacturer") "YAGEO(国巨)"))
      (libsource (lib "") (part "RT0402BRD071KL"))
    )
    (comp (ref "R20")
      (value "330Ω")
      (fields (field (name "Manufacturer Part") "RC0402JR-07330RL") (field (name "Manufacturer") "YAGEO(国巨)"))
      (libsource (lib "") (part "RC0402JR-07330RL_1"))
    )
    (comp (ref "R21")
      (value "330Ω")
      (fields (field (name "Manufacturer Part") "RC0402JR-07330RL") (field (name "Manufacturer") "YAGEO(国巨)"))
      (libsource (lib "") (part "RC0402JR-07330RL"))
    )
    (comp (ref "R22")
      (value "4.7kΩ")
      (fields (field (name "Manufacturer Part") "RC0402FR-074K7L") (field (name "Manufacturer") "YAGEO(国巨)"))
      (libsource (lib "") (part "RC0402FR-074K7L"))
    )
    (comp (ref "R23")
      (value "2.49kΩ")
      (fields (field (name "Manufacturer Part") "FRC0402F2491TS") (field (name "Manufacturer") "FOJAN(富捷)"))
      (libsource (lib "") (part "FRC0402F2491TS"))
    )
    (comp (ref "R24")
      (value "59kΩ")
      (fields (field (name "Manufacturer Part") "RS-03K5902FT") (field (name "Manufacturer") "FH(风华)"))
      (libsource (lib "") (part "RS-03K5902FT"))
    )
    (comp (ref "R25")
      (value "100kΩ")
      (fields (field (name "Manufacturer Part") "RS-03K1003FT") (field (name "Manufacturer") "FH(风华)"))
      (libsource (lib "") (part "RS-03K1003FT_C115320"))
    )
    (comp (ref "RJ1")
      (value "RT7-174AAM1A")
      (fields (field (name "Manufacturer") "UDE(涌德电子)"))
      (libsource (lib "") (part "RT7-174AAM1A"))
    )
    (comp (ref "U8")
      (value "RTL8125BG-CG")
      (fields (field (name "Manufacturer") "REALTEK(瑞昱)"))
      (libsource (lib "") (part "RTL8125BG-CG"))
    )
    (comp (ref "U9")
      (value "TLV62568DRLR")
      (fields (field (name "Manufacturer") "TI(德州仪器)"))
      (libsource (lib "") (part "TLV62568DRLR"))
    )
    (comp (ref "X1")
      (value "25MHz")
      (fields
        (field (name "Manufacturer Part") "SX3M25.000B10G40TNN")
        (field (name "Manufacturer") "SCTF(星通时频)")
      )
      (libsource (lib "") (part "SX3M25.000B10G40TNN"))
    )
    (comp (ref "C73")
      (value "100nF")
      (fields
        (field (name "Manufacturer Part") "GRM155R71H104KE14J")
        (field (name "Manufacturer") "muRata(村田)")
      )
      (libsource (lib "") (part "GRM155R71H104KE14J"))
    )
    (comp (ref "C74")
      (value "100nF")
      (fields
        (field (name "Manufacturer Part") "GRM155R71H104KE14J")
        (field (name "Manufacturer") "muRata(村田)")
      )
      (libsource (lib "") (part "GRM155R71H104KE14J"))
    )
    (comp (ref "C75")
      (value "150uF")
      (fields
        (field (name "Manufacturer Part") "GRM31CR60J157ME11L")
        (field (name "Manufacturer") "muRata(村田)")
      )
      (libsource (lib "") (part "GRM31CR60J157ME11L"))
    )
    (comp (ref "C76")
      (value "150uF")
      (fields
        (field (name "Manufacturer Part") "GRM31CR60J157ME11L")
        (field (name "Manufacturer") "muRata(村田)")
      )
      (libsource (lib "") (part "GRM31CR60J157ME11L"))
    )
    (comp (ref "C77")
      (value "150uF")
      (fields
        (field (name "Manufacturer Part") "GRM31CR60J157ME11L")
        (field (name "Manufacturer") "muRata(村田)")
      )
      (libsource (lib "") (part "GRM31CR60J157ME11L_1"))
    )
    (comp (ref "C78")
      (value "150uF")
      (fields
        (field (name "Manufacturer Part") "GRM31CR60J157ME11L")
        (field (name "Manufacturer") "muRata(村田)")
      )
      (libsource (lib "") (part "GRM31CR60J157ME11L"))
    )
    (comp (ref "C79")
      (value "100nF")
      (fields
        (field (name "Manufacturer Part") "GRM155R71H104KE14J")
        (field (name "Manufacturer") "muRata(村田)")
      )
      (libsource (lib "") (part "GRM155R71H104KE14J"))
    )
    (comp (ref "C80")
      (value "100nF")
      (fields
        (field (name "Manufacturer Part") "GRM155R71H104KE14J")
        (field (name "Manufacturer") "muRata(村田)")
      )
      (libsource (lib "") (part "GRM155R71H104KE14J"))
    )
    (comp (ref "C81")
      (value "100nF")
      (fields
        (field (name "Manufacturer Part") "GRM155R71H104KE14J")
        (field (name "Manufacturer") "muRata(村田)")
      )
      (libsource (lib "") (part "GRM155R71H104KE14J"))
    )
    (comp (ref "C82")
      (value "100nF")
      (fields
        (field (name "Manufacturer Part") "GRM155R71H104KE14J")
        (field (name "Manufacturer") "muRata(村田)")
      )
      (libsource (lib "") (part "GRM155R71H104KE14J"))
    )
    (comp (ref "C83")
      (value "100nF")
      (fields
        (field (name "Manufacturer Part") "GRM155R71H104KE14J")
        (field (name "Manufacturer") "muRata(村田)")
      )
      (libsource (lib "") (part "GRM155R71H104KE14J"))
    )
    (comp (ref "C84")
      (value "100nF")
      (fields
        (field (name "Manufacturer Part") "GRM155R71H104KE14J")
        (field (name "Manufacturer") "muRata(村田)")
      )
      (libsource (lib "") (part "GRM155R71H104KE14J"))
    )
    (comp (ref "C85")
      (value "30pF")
      (fields
        (field (name "Manufacturer Part") "TCC0402COG300J500AT")
        (field (name "Manufacturer") "CCTC(三环)")
      )
      (libsource (lib "") (part "TCC0402COG300J500AT"))
    )
    (comp (ref "C86")
      (value "30pF")
      (fields
        (field (name "Manufacturer Part") "TCC0402COG300J500AT")
        (field (name "Manufacturer") "CCTC(三环)")
      )
      (libsource (lib "") (part "TCC0402COG300J500AT"))
    )
    (comp (ref "C87")
      (value "100nF")
      (fields
        (field (name "Manufacturer Part") "GRM155R71H104KE14J")
        (field (name "Manufacturer") "muRata(村田)")
      )
      (libsource (lib "") (part "GRM155R71H104KE14J"))
    )
    (comp (ref "C88")
      (value "100nF")
      (fields
        (field (name "Manufacturer Part") "GRM155R71H104KE14J")
        (field (name "Manufacturer") "muRata(村田)")
      )
      (libsource (lib "") (part "GRM155R71H104KE14J"))
    )
    (comp (ref "C89")
      (value "100nF")
      (fields
        (field (name "Manufacturer Part") "GRM155R71H104KE14J")
        (field (name "Manufacturer") "muRata(村田)")
      )
      (libsource (lib "") (part "GRM155R71H104KE14J"))
    )
    (comp (ref "C90")
      (value "100nF")
      (fields
        (field (name "Manufacturer Part") "GRM155R71H104KE14J")
        (field (name "Manufacturer") "muRata(村田)")
      )
      (libsource (lib "") (part "GRM155R71H104KE14J"))
    )
    (comp (ref "C91")
      (value "100nF")
      (fields
        (field (name "Manufacturer Part") "GRM155R71H104KE14J")
        (field (name "Manufacturer") "muRata(村田)")
      )
      (libsource (lib "") (part "GRM155R71H104KE14J"))
    )
    (comp (ref "C92")
      (value "100nF")
      (fields
        (field (name "Manufacturer Part") "GRM155R71H104KE14J")
        (field (name "Manufacturer") "muRata(村田)")
      )
      (libsource (lib "") (part "GRM155R71H104KE14J"))
    )
    (comp (ref "C93")
      (value "100nF")
      (fields
        (field (name "Manufacturer Part") "GRM155R71H104KE14J")
        (field (name "Manufacturer") "muRata(村田)")
      )
      (libsource (lib "") (part "GRM155R71H104KE14J"))
    )
    (comp (ref "C94")
      (value "100nF")
      (fields
        (field (name "Manufacturer Part") "GRM155R71H104KE14J")
        (field (name "Manufacturer") "muRata(村田)")
      )
      (libsource (lib "") (part "GRM155R71H104KE14J"))
    )
    (comp (ref "C95")
      (value "100nF")
      (fields
        (field (name "Manufacturer Part") "GRM155R71H104KE14J")
        (field (name "Manufacturer") "muRata(村田)")
      )
      (libsource (lib "") (part "GRM155R71H104KE14J"))
    )
    (comp (ref "C96")
      (value "100nF")
      (fields
        (field (name "Manufacturer Part") "GRM155R71H104KE14J")
        (field (name "Manufacturer") "muRata(村田)")
      )
      (libsource (lib "") (part "GRM155R71H104KE14J"))
    )
    (comp (ref "C97")
      (value "100nF")
      (fields
        (field (name "Manufacturer Part") "GRM155R71H104KE14J")
        (field (name "Manufacturer") "muRata(村田)")
      )
      (libsource (lib "") (part "GRM155R71H104KE14J"))
    )
    (comp (ref "C98")
      (value "100nF")
      (fields
        (field (name "Manufacturer Part") "GRM155R71H104KE14J")
        (field (name "Manufacturer") "muRata(村田)")
      )
      (libsource (lib "") (part "GRM155R71H104KE14J"))
    )
    (comp (ref "C99")
      (value "100nF")
      (fields
        (field (name "Manufacturer Part") "GRM155R71H104KE14J")
        (field (name "Manufacturer") "muRata(村田)")
      )
      (libsource (lib "") (part "GRM155R71H104KE14J"))
    )
    (comp (ref "C100")
      (value "100nF")
      (fields
        (field (name "Manufacturer Part") "GRM155R71H104KE14J")
        (field (name "Manufacturer") "muRata(村田)")
      )
      (libsource (lib "") (part "GRM155R71H104KE14J"))
    )
    (comp (ref "C101")
      (value "100nF")
      (fields
        (field (name "Manufacturer Part") "GRM155R71H104KE14J")
        (field (name "Manufacturer") "muRata(村田)")
      )
      (libsource (lib "") (part "GRM155R71H104KE14J"))
    )
    (comp (ref "C102")
      (value "100nF")
      (fields
        (field (name "Manufacturer Part") "GRM155R71H104KE14J")
        (field (name "Manufacturer") "muRata(村田)")
      )
      (libsource (lib "") (part "GRM155R71H104KE14J"))
    )
    (comp (ref "C103")
      (value "100nF")
      (fields
        (field (name "Manufacturer Part") "GRM155R71H104KE14J")
        (field (name "Manufacturer") "muRata(村田)")
      )
      (libsource (lib "") (part "GRM155R71H104KE14J"))
    )
    (comp (ref "C104")
      (value "22uF")
      (fields
        (field (name "Manufacturer Part") "GRT21BR61E226ME13L")
        (field (name "Manufacturer") "muRata(村田)")
      )
      (libsource (lib "") (part "GRT21BR61E226ME13L"))
    )
    (comp (ref "C105")
      (value "100nF")
      (fields
        (field (name "Manufacturer Part") "GRM155R71H104KE14J")
        (field (name "Manufacturer") "muRata(村田)")
      )
      (libsource (lib "") (part "GRM155R71H104KE14J"))
    )
    (comp (ref "C106")
      (value "100nF")
      (fields
        (field (name "Manufacturer Part") "GRM155R71H104KE14J")
        (field (name "Manufacturer") "muRata(村田)")
      )
      (libsource (lib "") (part "GRM155R71H104KE14J"))
    )
    (comp (ref "C107")
      (value "100nF")
      (fields
        (field (name "Manufacturer Part") "GRM155R71H104KE14J")
        (field (name "Manufacturer") "muRata(村田)")
      )
      (libsource (lib "") (part "GRM155R71H104KE14J"))
    )
    (comp (ref "C108")
      (value "100nF")
      (fields
        (field (name "Manufacturer Part") "GRM155R71H104KE14J")
        (field (name "Manufacturer") "muRata(村田)")
      )
      (libsource (lib "") (part "GRM155R71H104KE14J"))
    )
    (comp (ref "C109")
      (value "22uF")
      (fields
        (field (name "Manufacturer Part") "GRT21BR61E226ME13L")
        (field (name "Manufacturer") "muRata(村田)")
      )
      (libsource (lib "") (part "GRT21BR61E226ME13L"))
    )
    (comp (ref "C110")
      (value "100nF")
      (fields
        (field (name "Manufacturer Part") "GRM155R71H104KE14J")
        (field (name "Manufacturer") "muRata(村田)")
      )
      (libsource (lib "") (part "GRM155R71H104KE14J_1"))
    )
    (comp (ref "D1")
      (value "USBLC6-2SC6")
      (fields (field (name "Manufacturer") "ST(意法半导体)"))
      (libsource (lib "") (part "USBLC6-2SC6"))
    )
    (comp (ref "D2")
      (value "SRV05-4_C2836319")
      (fields (field (name "Manufacturer Part") "SRV05-4") (field (name "Manufacturer") "MSKSEMI(美森科)"))
      (libsource (lib "") (part "SRV05-4_C2836319"))
    )
    (comp (ref "D3")
      (value "USBLC6-2SC6")
      (fields (field (name "Manufacturer") "ST(意法半导体)"))
      (libsource (lib "") (part "USBLC6-2SC6"))
    )
    (comp (ref "D4")
      (value "USBLC6-2SC6")
      (fields (field (name "Manufacturer") "ST(意法半导体)"))
      (libsource (lib "") (part "USBLC6-2SC6"))
    )
    (comp (ref "D5")
      (value "USBLC6-2SC6")
      (fields (field (name "Manufacturer") "ST(意法半导体)"))
      (libsource (lib "") (part "USBLC6-2SC6"))
    )
    (comp (ref "D6")
      (value "USBLC6-2SC6")
      (fields (field (name "Manufacturer") "ST(意法半导体)"))
      (libsource (lib "") (part "USBLC6-2SC6"))
    )
    (comp (ref "D7")
      (value "USBLC6-2SC6")
      (fields (field (name "Manufacturer") "ST(意法半导体)"))
      (libsource (lib "") (part "USBLC6-2SC6"))
    )
    (comp (ref "D8")
      (value "SRV05-4_C2836319")
      (fields (field (name "Manufacturer Part") "SRV05-4") (field (name "Manufacturer") "MSKSEMI(美森科)"))
      (libsource (lib "") (part "SRV05-4_C2836319"))
    )
    (comp (ref "L4")
      (value "2.2uH")
      (fields (field (name "Manufacturer Part") "MLP2012H2R2MT0S1") (field (name "Manufacturer") "TDK"))
      (libsource (lib "") (part "MLP2012H2R2MT0S1"))
    )
    (comp (ref "R26")
      (value "10kΩ")
      (fields (field (name "Manufacturer Part") "FRC0402F1002TS") (field (name "Manufacturer") "FOJAN(富捷)"))
      (libsource (lib "") (part "FRC0402F1002TS_1"))
    )
    (comp (ref "R27")
      (value "10kΩ")
      (fields (field (name "Manufacturer Part") "FRC0402F1002TS") (field (name "Manufacturer") "FOJAN(富捷)"))
      (libsource (lib "") (part "FRC0402F1002TS_1"))
    )
    (comp (ref "R28")
      (value "10kΩ")
      (fields (field (name "Manufacturer Part") "FRC0402F1002TS") (field (name "Manufacturer") "FOJAN(富捷)"))
      (libsource (lib "") (part "FRC0402F1002TS_1"))
    )
    (comp (ref "R29")
      (value "10kΩ")
      (fields (field (name "Manufacturer Part") "FRC0402F1002TS") (field (name "Manufacturer") "FOJAN(富捷)"))
      (libsource (lib "") (part "FRC0402F1002TS_1"))
    )
    (comp (ref "R30")
      (value "10kΩ")
      (fields (field (name "Manufacturer Part") "FRC0402F1002TS") (field (name "Manufacturer") "FOJAN(富捷)"))
      (libsource (lib "") (part "FRC0402F1002TS_1"))
    )
    (comp (ref "R31")
      (value "10kΩ")
      (fields (field (name "Manufacturer Part") "FRC0402F1002TS") (field (name "Manufacturer") "FOJAN(富捷)"))
      (libsource (lib "") (part "FRC0402F1002TS_1"))
    )
    (comp (ref "R32")
      (value "10kΩ")
      (fields (field (name "Manufacturer Part") "FRC0402F1002TS") (field (name "Manufacturer") "FOJAN(富捷)"))
      (libsource (lib "") (part "FRC0402F1002TS_2"))
    )
    (comp (ref "R33")
      (value "10kΩ")
      (fields (field (name "Manufacturer Part") "FRC0402F1002TS") (field (name "Manufacturer") "FOJAN(富捷)"))
      (libsource (lib "") (part "FRC0402F1002TS"))
    )
    (comp (ref "R34")
      (value "10kΩ")
      (fields (field (name "Manufacturer Part") "FRC0402F1002TS") (field (name "Manufacturer") "FOJAN(富捷)"))
      (libsource (lib "") (part "FRC0402F1002TS"))
    )
    (comp (ref "R35")
      (value "10kΩ")
      (fields (field (name "Manufacturer Part") "FRC0402F1002TS") (field (name "Manufacturer") "FOJAN(富捷)"))
      (libsource (lib "") (part "FRC0402F1002TS"))
    )
    (comp (ref "R36")
      (value "10kΩ")
      (fields (field (name "Manufacturer Part") "FRC0402F1002TS") (field (name "Manufacturer") "FOJAN(富捷)"))
      (libsource (lib "") (part "FRC0402F1002TS"))
    )
    (comp (ref "R37")
      (value "10kΩ")
      (fields (field (name "Manufacturer Part") "FRC0402F1002TS") (field (name "Manufacturer") "FOJAN(富捷)"))
      (libsource (lib "") (part "FRC0402F1002TS"))
    )
    (comp (ref "R38")
      (value "100kΩ")
      (fields (field (name "Manufacturer Part") "RS-03K1003FT") (field (name "Manufacturer") "FH(风华)"))
      (libsource (lib "") (part "RS-03K1003FT_C115320"))
    )
    (comp (ref "R39")
      (value "75kΩ")
      (fields (field (name "Manufacturer Part") "RS-03K7502FT") (field (name "Manufacturer") "FH(风华)"))
      (libsource (lib "") (part "RS-03K7502FT"))
    )
    (comp (ref "R40")
      (value "10kΩ")
      (fields (field (name "Manufacturer Part") "FRC0402F1002TS") (field (name "Manufacturer") "FOJAN(富捷)"))
      (libsource (lib "") (part "FRC0402F1002TS"))
    )
    (comp (ref "R41")
      (value "10kΩ")
      (fields (field (name "Manufacturer Part") "FRC0402F1002TS") (field (name "Manufacturer") "FOJAN(富捷)"))
      (libsource (lib "") (part "FRC0402F1002TS_1"))
    )
    (comp (ref "R42")
      (value "10kΩ")
      (fields (field (name "Manufacturer Part") "FRC0402F1002TS") (field (name "Manufacturer") "FOJAN(富捷)"))
      (libsource (lib "") (part "FRC0402F1002TS_1"))
    )
    (comp (ref "U10")
      (value "UPD720201K8-701-BAC-A")
      (fields (field (name "Manufacturer") "RENESAS(瑞萨)/IDT"))
      (libsource (lib "") (part "UPD720201K8-701-BAC-A"))
    )
    (comp (ref "U11")
      (value "1932258-1")
      (fields (field (name "Manufacturer") "TE Connectivity(泰科电子)"))
      (libsource (lib "") (part "1932258-1"))
    )
    (comp (ref "U12")
      (value "1932258-1")
      (fields (field (name "Manufacturer") "TE Connectivity(泰科电子)"))
      (libsource (lib "") (part "1932258-1"))
    )
    (comp (ref "U13")
      (value "TPS2062CDR")
      (fields (field (name "Manufacturer") "TI(德州仪器)"))
      (libsource (lib "") (part "TPS2062CDR"))
    )
    (comp (ref "U14")
      (value "TPS2052BDR")
      (fields (field (name "Manufacturer") "TI(德州仪器)"))
      (libsource (lib "") (part "TPS2052BDR"))
    )
    (comp (ref "U15")
      (value "TPS2052BDR")
      (fields (field (name "Manufacturer") "TI(德州仪器)"))
      (libsource (lib "") (part "TPS2052BDR"))
    )
    (comp (ref "U16")
      (value "W25Q80DVUXIE")
      (fields (field (name "Manufacturer") "Winbond(华邦)"))
      (libsource (lib "") (part "W25Q80DVUXIE"))
    )
    (comp (ref "U17")
      (value "TLV62568DRLR")
      (fields (field (name "Manufacturer") "TI(德州仪器)"))
      (libsource (lib "") (part "TLV62568DRLR"))
    )
    (comp (ref "USB1")
      (value "USB-269-BRW")
      (fields (field (name "Manufacturer") "XUNPU(讯普)"))
      (libsource (lib "") (part "USB-269-BRW"))
    )
    (comp (ref "USB2")
      (value "USB-269-BRW")
      (fields (field (name "Manufacturer") "XUNPU(讯普)"))
      (libsource (lib "") (part "USB-269-BRW"))
    )
    (comp (ref "X2")
      (value "24MHz")
      (fields
        (field (name "Manufacturer Part") "ABM7-24.000MHZ-D2Y-T")
        (field (name "Manufacturer") "ABRACON")
      )
      (libsource (lib "") (part "ABM7-24.000MHZ-D2Y-T"))
    )
  )
  (nets
    (net (code "1") (name "+5V") (class "Default")
      (node (ref "C13") (pin "2") (pinfunction "2_2") (pintype "unspecified"))
      (node (ref "C14") (pin "2") (pinfunction "2_2") (pintype "unspecified"))
      (node (ref "C15") (pin "2") (pinfunction "2_2") (pintype "unspecified"))
      (node (ref "C24") (pin "2") (pinfunction "2_2") (pintype "unspecified"))
      (node (ref "C25") (pin "2") (pinfunction "2_2") (pintype "unspecified"))
      (node (ref "C26") (pin "2") (pinfunction "2_2") (pintype "unspecified"))
      (node (ref "C3") (pin "1") (pinfunction "1_1") (pintype "unspecified"))
      (node (ref "C4") (pin "1") (pinfunction "1_1") (pintype "unspecified"))
      (node (ref "C73") (pin "1") (pinfunction "1_1") (pintype "unspecified"))
      (node (ref "C74") (pin "1") (pinfunction "1_1") (pintype "unspecified"))
      (node (ref "R3") (pin "1") (pinfunction "1_1") (pintype "unspecified"))
      (node (ref "U13") (pin "2") (pinfunction "IN_2") (pintype "unspecified"))
      (node (ref "U14") (pin "2") (pinfunction "IN_2") (pintype "input"))
      (node (ref "U15") (pin "2") (pinfunction "IN_2") (pintype "input"))
      (node (ref "U2") (pin "2") (pinfunction "2_2") (pintype "unspecified"))
      (node (ref "U3") (pin "2") (pinfunction "2_2") (pintype "unspecified"))
      (node (ref "U4") (pin "2") (pinfunction "2_2") (pintype "unspecified"))
    )
    (net (code "2") (name "1V05") (class "Default")
      (node (ref "C101") (pin "2") (pinfunction "2_2") (pintype "unspecified"))
      (node (ref "C102") (pin "2") (pinfunction "2_2") (pintype "unspecified"))
      (node (ref "C109") (pin "1") (pinfunction "1_1") (pintype "unspecified"))
      (node (ref "C88") (pin "2") (pinfunction "2_2") (pintype "unspecified"))
      (node (ref "C90") (pin "1") (pinfunction "1_1") (pintype "unspecified"))
      (node (ref "C92") (pin "1") (pinfunction "1_1") (pintype "unspecified"))
      (node (ref "C95") (pin "1") (pinfunction "1_1") (pintype "unspecified"))
      (node (ref "C97") (pin "1") (pinfunction "1_1") (pintype "unspecified"))
      (node (ref "C98") (pin "1") (pinfunction "1_1") (pintype "unspecified"))
      (node (ref "L4") (pin "2") (pinfunction "2_2") (pintype "unspecified"))
      (node (ref "R39") (pin "2") (pinfunction "2_2") (pintype "input"))
      (node (ref "U10") (pin "12") (pinfunction "VDD10_12") (pintype "unspecified"))
      (node (ref "U10") (pin "28") (pinfunction "VDD10_28") (pintype "unspecified"))
      (node (ref "U10") (pin "37") (pinfunction "VDD10_37") (pintype "unspecified"))
      (node (ref "U10") (pin "43") (pinfunction "VDD10_43") (pintype "unspecified"))
      (node (ref "U10") (pin "54") (pinfunction "VDD10_54") (pintype "unspecified"))
      (node (ref "U10") (pin "60") (pinfunction "VDD10_60") (pintype "unspecified"))
      (node (ref "U10") (pin "63") (pinfunction "VDD10_63") (pintype "unspecified"))
      (node (ref "U10") (pin "9") (pinfunction "VDD10_9") (pintype "unspecified"))
    )
    (net (code "3") (name "1V05_PG") (class "Default")
      (node (ref "C110") (pin "2") (pinfunction "2_2") (pintype "unspecified"))
      (node (ref "R40") (pin "1") (pinfunction "1_1") (pintype "unspecified"))
      (node (ref "U10") (pin "14") (pinfunction "PONRSTB_14") (pintype "unspecified"))
      (node (ref "U17") (pin "6") (pinfunction "NC/PG_6") (pintype "unspecified"))
    )
    (net (code "4") (name "3V3M") (class "Default")
      (node (ref "C100") (pin "2") (pinfunction "2_2") (pintype "unspecified"))
      (node (ref "C103") (pin "2") (pinfunction "2_2") (pintype "unspecified"))
      (node (ref "C104") (pin "2") (pinfunction "2_2") (pintype "unspecified"))
      (node (ref "C27") (pin "2") (pinfunction "2_2") (pintype "unspecified"))
      (node (ref "C28") (pin "2") (pinfunction "2_2") (pintype "unspecified"))
      (node (ref "C38") (pin "2") (pinfunction "2_2") (pintype "input"))
      (node (ref "C39") (pin "2") (pinfunction "2_2") (pintype "input"))
      (node (ref "C40") (pin "2") (pinfunction "2_2") (pintype "input"))
      (node (ref "C41") (pin "2") (pinfunction "2_2") (pintype "input"))
      (node (ref "C42") (pin "2") (pinfunction "2_2") (pintype "input"))
      (node (ref "C5") (pin "1") (pinfunction "1_1") (pintype "unspecified"))
      (node (ref "C6") (pin "1") (pinfunction "1_1") (pintype "unspecified"))
      (node (ref "C87") (pin "2") (pinfunction "2_2") (pintype "unspecified"))
      (node (ref "C89") (pin "2") (pinfunction "2_2") (pintype "unspecified"))
      (node (ref "C91") (pin "1") (pinfunction "1_1") (pintype "unspecified"))
      (node (ref "C94") (pin "1") (pinfunction "1_1") (pintype "unspecified"))
      (node (ref "C96") (pin "1") (pinfunction "1_1") (pintype "unspecified"))
      (node (ref "C99") (pin "1") (pinfunction "1_1") (pintype "unspecified"))
      (node (ref "L1") (pin "2") (pinfunction "2_2") (pintype "unspecified"))
      (node (ref "L2") (pin "2") (pinfunction "2_2") (pintype "unspecified"))
      (node (ref "R14") (pin "2") (pinfunction "2_2") (pintype "unspecified"))
      (node (ref "R15") (pin "2") (pinfunction "2_2") (pintype "unspecified"))
      (node (ref "R16") (pin "2") (pinfunction "2_2") (pintype "unspecified"))
      (node (ref "R26") (pin "2") (pinfunction "2_2") (pintype "unspecified"))
      (node (ref "R27") (pin "2") (pinfunction "2_2") (pintype "unspecified"))
      (node (ref "R28") (pin "1") (pinfunction "1_1") (pintype "unspecified"))
      (node (ref "R29") (pin "1") (pinfunction "1_1") (pintype "unspecified"))
      (node (ref "R30") (pin "2") (pinfunction "2_2") (pintype "unspecified"))
      (node (ref "R31") (pin "2") (pinfunction "2_2") (pintype "unspecified"))
      (node (ref "R32") (pin "2") (pinfunction "2_2") (pintype "unspecified"))
      (node (ref "R33") (pin "2") (pinfunction "2_2") (pintype "unspecified"))
      (node (ref "R34") (pin "2") (pinfunction "2_2") (pintype "unspecified"))
      (node (ref "R40") (pin "2") (pinfunction "2_2") (pintype "unspecified"))
      (node (ref "R41") (pin "2") (pinfunction "2_2") (pintype "unspecified"))
      (node (ref "R42") (pin "2") (pinfunction "2_2") (pintype "unspecified"))
      (node (ref "U10") (pin "15") (pinfunction "VDD33_15") (pintype "unspecified"))
      (node (ref "U10") (pin "29") (pinfunction "VDD33_29") (pintype "unspecified"))
      (node (ref "U10") (pin "32") (pinfunction "AVDD33_32") (pintype "unspecified"))
      (node (ref "U10") (pin "40") (pinfunction "VDD33_40") (pintype "unspecified"))
      (node (ref "U10") (pin "49") (pinfunction "VDD33_49") (pintype "unspecified"))
      (node (ref "U10") (pin "57") (pinfunction "VDD33_57") (pintype "unspecified"))
      (node (ref "U10") (pin "6") (pinfunction "AVDD33_6") (pintype "unspecified"))
      (node (ref "U10") (pin "66") (pinfunction "VDD33_66") (pintype "unspecified"))
      (node (ref "U16") (pin "8") (pinfunction "VCC_8") (pintype "unspecified"))
      (node (ref "U17") (pin "3") (pinfunction "VIN_3") (pintype "unspecified"))
      (node (ref "U17") (pin "5") (pinfunction "EN_5") (pintype "unspecified"))
      (node (ref "U9") (pin "3") (pinfunction "VIN_3") (pintype "unspecified"))
    )
    (net (code "5") (name "3V3_WIFI") (class "Default")
      (node (ref "C29") (pin "1") (pinfunction "1_1") (pintype "unspecified"))
      (node (ref "C30") (pin "2") (pinfunction "2_2") (pintype "unspecified"))
      (node (ref "C31") (pin "1") (pinfunction "1_1") (pintype "unspecified"))
      (node (ref "C32") (pin "2") (pinfunction "2_2") (pintype "unspecified"))
      (node (ref "C36") (pin "2") (pinfunction "2_2") (pintype "unspecified"))
      (node (ref "C37") (pin "2") (pinfunction "2_2") (pintype "unspecified"))
      (node (ref "L1") (pin "1") (pinfunction "1_1") (pintype "unspecified"))
      (node (ref "R12") (pin "1") (pinfunction "1_1") (pintype "unspecified"))
      (node (ref "R13") (pin "1") (pinfunction "1_1") (pintype "unspecified"))
      (node (ref "R9") (pin "2") (pinfunction "2_2") (pintype "unspecified"))
      (node (ref "U6") (pin "2") (pinfunction "2_2") (pintype "unspecified"))
      (node (ref "U6") (pin "4") (pinfunction "4_4") (pintype "unspecified"))
      (node (ref "U6") (pin "72") (pinfunction "72_72") (pintype "unspecified"))
      (node (ref "U6") (pin "74") (pinfunction "74_74") (pintype "unspecified"))
    )
    (net (code "6") (name "9ETH") (class "Default")
      (node (ref "C58") (pin "1") (pinfunction "1_1") (pintype "unspecified"))
      (node (ref "C59") (pin "2") (pinfunction "2_2") (pintype "unspecified"))
      (node (ref "C61") (pin "2") (pinfunction "2_2") (pintype "unspecified"))
      (node (ref "C63") (pin "2") (pinfunction "2_2") (pintype "unspecified"))
      (node (ref "C64") (pin "1") (pinfunction "1_1") (pintype "unspecified"))
      (node (ref "C67") (pin "1") (pinfunction "1_1") (pintype "unspecified"))
      (node (ref "C71") (pin "1") (pinfunction "1_1") (pintype "unspecified"))
      (node (ref "C72") (pin "2") (pinfunction "2_2") (pintype "unspecified"))
      (node (ref "L3") (pin "2") (pinfunction "2_2") (pintype "unspecified"))
      (node (ref "R24") (pin "2") (pinfunction "2_2") (pintype "unspecified"))
      (node (ref "U8") (pin "11") (pinfunction "AVDD09_11") (pintype "unspecified"))
      (node (ref "U8") (pin "16") (pinfunction "AVDD09_16") (pintype "unspecified"))
      (node (ref "U8") (pin "22") (pinfunction "AVDD09_22") (pintype "unspecified"))
      (node (ref "U8") (pin "28") (pinfunction "DVDD09_28") (pintype "unspecified"))
      (node (ref "U8") (pin "37") (pinfunction "EVDD09_37") (pintype "unspecified"))
      (node (ref "U8") (pin "47") (pinfunction "DVDD09_47") (pintype "unspecified"))
      (node (ref "U8") (pin "8") (pinfunction "DVDD09_8") (pintype "unspecified"))
    )
    (net (code "7") (name "19V_SYS") (class "Default")
      (node (ref "C10") (pin "1") (pinfunction "1_1") (pintype "unspecified"))
      (node (ref "C11") (pin "1") (pinfunction "1_1") (pintype "unspecified"))
      (node (ref "C12") (pin "1") (pinfunction "1_1") (pintype "unspecified"))
      (node (ref "C9") (pin "1") (pinfunction "1_1") (pintype "unspecified"))
      (node (ref "DC1") (pin "6") (pinfunction "6_6") (pintype "unspecified"))
      (node (ref "R1") (pin "1") (pinfunction "1_1") (pintype "unspecified"))
      (node (ref "R11") (pin "1") (pinfunction "1_1") (pintype "unspecified"))
      (node (ref "U1") (pin "2") (pinfunction "VIN_2") (pintype "unspecified"))
      (node (ref "U5") (pin "2") (pinfunction "VIN_2") (pintype "unspecified"))
    )
    (net (code "8") (name "BL_USB_N") (class "Default")
      (node (ref "U6") (pin "5") (pinfunction "5_5") (pintype "unspecified"))
    )
    (net (code "9") (name "BL_USB_P") (class "Default")
      (node (ref "U6") (pin "3") (pinfunction "3_3") (pintype "unspecified"))
    )
    (net (code "10") (name "CLOCK_ETH") (class "Default")
      (node (ref "U8") (pin "10") (pinfunction "CKXTAL1_10") (pintype "unspecified"))
      (node (ref "X1") (pin "3") (pinfunction "OUTPUT_3") (pintype "unspecified"))
    )
    (net (code "11") (name "ETH_CLKREQ_N") (class "Default")
      (node (ref "R17") (pin "1") (pinfunction "1_1") (pintype "input"))
      (node (ref "U8") (pin "48") (pinfunction "CLKREQB_48") (pintype "unspecified"))
    )
    (net (code "12") (name "ETH_CLK_N") (class "Default")
      (node (ref "U8") (pin "45") (pinfunction "REFCLK_N_45") (pintype "unspecified"))
    )
    (net (code "13") (name "ETH_CLK_P") (class "Default")
      (node (ref "U8") (pin "44") (pinfunction "REFCLK_P_44") (pintype "unspecified"))
    )
    (net (code "14") (name "ETH_MDI0_N") (class "Default")
      (node (ref "RJ1") (pin "R2") (pinfunction "TD1-_R2") (pintype "unspecified"))
      (node (ref "U8") (pin "14") (pinfunction "MDIN0_14") (pintype "unspecified"))
    )
    (net (code "15") (name "ETH_MDI0_P") (class "Default")
      (node (ref "RJ1") (pin "R1") (pinfunction "TD1+_R1") (pintype "unspecified"))
      (node (ref "U8") (pin "13") (pinfunction "MDIP0_13") (pintype "unspecified"))
    )
    (net (code "16") (name "ETH_MDI1_N") (class "Default")
      (node (ref "RJ1") (pin "R4") (pinfunction "TD2-_R4") (pintype "unspecified"))
      (node (ref "U8") (pin "18") (pinfunction "MDIN1_18") (pintype "unspecified"))
    )
    (net (code "17") (name "ETH_MDI1_P") (class "Default")
      (node (ref "RJ1") (pin "R3") (pinfunction "TD2+_R3") (pintype "unspecified"))
      (node (ref "U8") (pin "17") (pinfunction "MDIP1_17") (pintype "unspecified"))
    )
    (net (code "18") (name "ETH_MDI2_N") (class "Default")
      (node (ref "RJ1") (pin "R8") (pinfunction "TD3-_R8") (pintype "unspecified"))
      (node (ref "U8") (pin "21") (pinfunction "MDIN2_21") (pintype "unspecified"))
    )
    (net (code "19") (name "ETH_MDI2_P") (class "Default")
      (node (ref "RJ1") (pin "R7") (pinfunction "TD3+_R7") (pintype "unspecified"))
      (node (ref "U8") (pin "20") (pinfunction "MDIP2_20") (pintype "unspecified"))
    )
    (net (code "20") (name "ETH_MDI3_N") (class "Default")
      (node (ref "RJ1") (pin "R9") (pinfunction "TD4+_R9") (pintype "unspecified"))
      (node (ref "U8") (pin "24") (pinfunction "MDIN3_24") (pintype "unspecified"))
    )
    (net (code "21") (name "ETH_MDI3_P") (class "Default")
      (node (ref "RJ1") (pin "R10") (pinfunction "TD4-_R10") (pintype "unspecified"))
      (node (ref "U8") (pin "23") (pinfunction "MDIP3_23") (pintype "unspecified"))
    )
    (net (code "22") (name "ETH_RST_N") (class "Default")
      (node (ref "R10") (pin "2") (pinfunction "2_2") (pintype "input"))
      (node (ref "U8") (pin "36") (pinfunction "PERSTB_36") (pintype "unspecified"))
    )
    (net (code "23") (name "ETH_RX_N") (class "Default")
      (node (ref "C56") (pin "2") (pinfunction "2_2") (pintype "unspecified"))
    )
    (net (code "24") (name "ETH_RX_P") (class "Default")
      (node (ref "C1") (pin "2") (pinfunction "2_2") (pintype "unspecified"))
      (node (ref "C10") (pin "2") (pinfunction "2_2") (pintype "unspecified"))
      (node (ref "C100") (pin "1") (pinfunction "1_1") (pintype "unspecified"))
      (node (ref "C101") (pin "1") (pinfunction "1_1") (pintype "unspecified"))
      (node (ref "C102") (pin "1") (pinfunction "1_1") (pintype "unspecified"))
      (node (ref "C103") (pin "1") (pinfunction "1_1") (pintype "unspecified"))
      (node (ref "C104") (pin "1") (pinfunction "1_1") (pintype "unspecified"))
      (node (ref "C109") (pin "2") (pinfunction "2_2") (pintype "unspecified"))
      (node (ref "C11") (pin "2") (pinfunction "2_2") (pintype "unspecified"))
      (node (ref "C110") (pin "1") (pinfunction "1_1") (pintype "unspecified"))
      (node (ref "C12") (pin "2") (pinfunction "2_2") (pintype "unspecified"))
      (node (ref "C27") (pin "1") (pinfunction "1_1") (pintype "unspecified"))
      (node (ref "C28") (pin "1") (pinfunction "1_1") (pintype "unspecified"))
      (node (ref "C29") (pin "2") (pinfunction "2_2") (pintype "unspecified"))
      (node (ref "C3") (pin "2") (pinfunction "2_2") (pintype "unspecified"))
      (node (ref "C30") (pin "1") (pinfunction "1_1") (pintype "unspecified"))
      (node (ref "C31") (pin "2") (pinfunction "2_2") (pintype "unspecified"))
      (node (ref "C32") (pin "1") (pinfunction "1_1") (pintype "unspecified"))
      (node (ref "C35") (pin "1") (pinfunction "1_1") (pintype "unspecified"))
      (node (ref "C36") (pin "1") (pinfunction "1_1") (pintype "unspecified"))
      (node (ref "C37") (pin "1") (pinfunction "1_1") (pintype "unspecified"))
      (node (ref "C4") (pin "2") (pinfunction "2_2") (pintype "unspecified"))
      (node (ref "C43") (pin "2") (pinfunction "2_2") (pintype "unspecified"))
      (node (ref "C5") (pin "2") (pinfunction "2_2") (pintype "unspecified"))
      (node (ref "C53") (pin "2") (pinfunction "2_2") (pintype "unspecified"))
      (node (ref "C54") (pin "1") (pinfunction "1_1") (pintype "unspecified"))
      (node (ref "C55") (pin "1") (pinfunction "1_1") (pintype "unspecified"))
      (node (ref "C57") (pin "2") (pinfunction "2_2") (pintype "unspecified"))
      (node (ref "C58") (pin "2") (pinfunction "2_2") (pintype "unspecified"))
      (node (ref "C59") (pin "1") (pinfunction "1_1") (pintype "unspecified"))
      (node (ref "C6") (pin "2") (pinfunction "2_2") (pintype "unspecified"))
      (node (ref "C60") (pin "1") (pinfunction "1_1") (pintype "unspecified"))
      (node (ref "C61") (pin "1") (pinfunction "1_1") (pintype "unspecified"))
      (node (ref "C62") (pin "1") (pinfunction "1_1") (pintype "unspecified"))
      (node (ref "C63") (pin "1") (pinfunction "1_1") (pintype "unspecified"))
      (node (ref "C64") (pin "2") (pinfunction "2_2") (pintype "unspecified"))
      (node (ref "C65") (pin "2") (pinfunction "2_2") (pintype "unspecified"))
      (node (ref "C66") (pin "2") (pinfunction "2_2") (pintype "unspecified"))
      (node (ref "C67") (pin "2") (pinfunction "2_2") (pintype "unspecified"))
      (node (ref "C68") (pin "2") (pinfunction "2_2") (pintype "unspecified"))
      (node (ref "C69") (pin "2") (pinfunction "2_2") (pintype "unspecified"))
      (node (ref "C70") (pin "2") (pinfunction "2_2") (pintype "unspecified"))
      (node (ref "C71") (pin "2") (pinfunction "2_2") (pintype "unspecified"))
      (node (ref "C72") (pin "1") (pinfunction "1_1") (pintype "unspecified"))
      (node (ref "C73") (pin "2") (pinfunction "2_2") (pintype "unspecified"))
      (node (ref "C74") (pin "2") (pinfunction "2_2") (pintype "unspecified"))
      (node (ref "C75") (pin "1") (pinfunction "1_1") (pintype "unspecified"))
      (node (ref "C76") (pin "1") (pinfunction "1_1") (pintype "unspecified"))
      (node (ref "C77") (pin "2") (pinfunction "2_2") (pintype "unspecified"))
      (node (ref "C78") (pin "1") (pinfunction "1_1") (pintype "unspecified"))
      (node (ref "C79") (pin "1") (pinfunction "1_1") (pintype "unspecified"))
      (node (ref "C8") (pin "2") (pinfunction "2_2") (pintype "unspecified"))
      (node (ref "C80") (pin "1") (pinfunction "1_1") (pintype "unspecified"))
      (node (ref "C81") (pin "1") (pinfunction "1_1") (pintype "unspecified"))
      (node (ref "C82") (pin "1") (pinfunction "1_1") (pintype "unspecified"))
      (node (ref "C85") (pin "1") (pinfunction "1_1") (pintype "unspecified"))
      (node (ref "C86") (pin "1") (pinfunction "1_1") (pintype "unspecified"))
      (node (ref "C87") (pin "1") (pinfunction "1_1") (pintype "unspecified"))
      (node (ref "C88") (pin "1") (pinfunction "1_1") (pintype "unspecified"))
      (node (ref "C89") (pin "1") (pinfunction "1_1") (pintype "unspecified"))
      (node (ref "C9") (pin "2") (pinfunction "2_2") (pintype "unspecified"))
      (node (ref "C90") (pin "2") (pinfunction "2_2") (pintype "unspecified"))
      (node (ref "C91") (pin "2") (pinfunction "2_2") (pintype "unspecified"))
      (node (ref "C92") (pin "2") (pinfunction "2_2") (pintype "unspecified"))
      (node (ref "C93") (pin "2") (pinfunction "2_2") (pintype "unspecified"))
      (node (ref "C94") (pin "2") (pinfunction "2_2") (pintype "unspecified"))
      (node (ref "C95") (pin "2") (pinfunction "2_2") (pintype "unspecified"))
      (node (ref "C96") (pin "2") (pinfunction "2_2") (pintype "unspecified"))
      (node (ref "C97") (pin "2") (pinfunction "2_2") (pintype "unspecified"))
      (node (ref "C98") (pin "2") (pinfunction "2_2") (pintype "unspecified"))
      (node (ref "C99") (pin "2") (pinfunction "2_2") (pintype "unspecified"))
      (node (ref "CN1") (pin "1") (pinfunction "S1_1") (pintype "unspecified"))
      (node (ref "CN1") (pin "11") (pinfunction "P4_11") (pintype "unspecified"))
      (node (ref "CN1") (pin "12") (pinfunction "P5_12") (pintype "unspecified"))
      (node (ref "CN1") (pin "13") (pinfunction "P6_13") (pintype "unspecified"))
      (node (ref "CN1") (pin "17") (pinfunction "P10_17") (pintype "unspecified"))
      (node (ref "CN1") (pin "18") (pinfunction "P11_18") (pintype "unspecified"))
      (node (ref "CN1") (pin "19") (pinfunction "P12_19") (pintype "unspecified"))
      (node (ref "CN1") (pin "23") (pinfunction "SHELL_23") (pintype "unspecified"))
      (node (ref "CN1") (pin "24") (pinfunction "SHELL_24") (pintype "unspecified"))
      (node (ref "CN1") (pin "4") (pinfunction "S4_4") (pintype "unspecified"))
      (node (ref "CN1") (pin "7") (pinfunction "S7_7") (pintype "unspecified"))
      (node (ref "CN2") (pin "1") (pinfunction "S1_1") (pintype "unspecified"))
      (node (ref "CN2") (pin "11") (pinfunction "P4_11") (pintype "unspecified"))
      (node (ref "CN2") (pin "12") (pinfunction "P5_12") (pintype "unspecified"))
      (node (ref "CN2") (pin "13") (pinfunction "P6_13") (pintype "unspecified"))
      (node (ref "CN2") (pin "17") (pinfunction "P10_17") (pintype "unspecified"))
      (node (ref "CN2") (pin "18") (pinfunction "P11_18") (pintype "unspecified"))
      (node (ref "CN2") (pin "19") (pinfunction "P12_19") (pintype "unspecified"))
      (node (ref "CN2") (pin "23") (pinfunction "SHELL_23") (pintype "unspecified"))
      (node (ref "CN2") (pin "24") (pinfunction "SHELL_24") (pintype "unspecified"))
      (node (ref "CN2") (pin "4") (pinfunction "S4_4") (pintype "unspecified"))
      (node (ref "CN2") (pin "7") (pinfunction "S7_7") (pintype "unspecified"))
      (node (ref "D1") (pin "2") (pinfunction "2_2") (pintype "input"))
      (node (ref "D3") (pin "2") (pinfunction "2_2") (pintype "input"))
      (node (ref "D4") (pin "2") (pinfunction "2_2") (pintype "input"))
      (node (ref "D5") (pin "2") (pinfunction "2_2") (pintype "input"))
      (node (ref "DC1") (pin "2") (pinfunction "2_2") (pintype "unspecified"))
      (node (ref "DC1") (pin "3") (pinfunction "3_3") (pintype "unspecified"))
      (node (ref "DC1") (pin "5") (pinfunction "5_5") (pintype "unspecified"))
      (node (ref "R23") (pin "1") (pinfunction "1_1") (pintype "unspecified"))
      (node (ref "R25") (pin "2") (pinfunction "2_2") (pintype "unspecified"))
      (node (ref "R35") (pin "2") (pinfunction "2_2") (pintype "unspecified"))
      (node (ref "R36") (pin "2") (pinfunction "2_2") (pintype "unspecified"))
      (node (ref "R37") (pin "2") (pinfunction "2_2") (pintype "unspecified"))
      (node (ref "R38") (pin "2") (pinfunction "2_2") (pintype "unspecified"))
      (node (ref "R4") (pin "1") (pinfunction "1_1") (pintype "unspecified"))
      (node (ref "R6") (pin "1") (pinfunction "1_1") (pintype "unspecified"))
      (node (ref "R7") (pin "1") (pinfunction "1_1") (pintype "unspecified"))
      (node (ref "R8") (pin "1") (pinfunction "1_1") (pintype "unspecified"))
      (node (ref "RJ1") (pin "1") (pinfunction "GND_1") (pintype "unspecified"))
      (node (ref "RJ1") (pin "2") (pinfunction "GND_2") (pintype "unspecified"))
      (node (ref "U1") (pin "7") (pinfunction "GND_7") (pintype "unspecified"))
      (node (ref "U1") (pin "9") (pinfunction "EP_9") (pintype "unspecified"))
      (node (ref "U10") (pin "34") (pinfunction "IC(L)_34") (pintype "unspecified"))
      (node (ref "U10") (pin "69") (pinfunction "EP_69") (pintype "unspecified"))
      (node (ref "U13") (pin "1") (pinfunction "GND_1") (pintype "unspecified"))
      (node (ref "U14") (pin "1") (pinfunction "GND_1") (pintype "unspecified"))
      (node (ref "U15") (pin "1") (pinfunction "GND_1") (pintype "unspecified"))
      (node (ref "U16") (pin "4") (pinfunction "GND_4") (pintype "unspecified"))
      (node (ref "U16") (pin "9") (pinfunction "EP_9") (pintype "unspecified"))
      (node (ref "U17") (pin "2") (pinfunction "GND_2") (pintype "unspecified"))
      (node (ref "U5") (pin "7") (pinfunction "GND_7") (pintype "unspecified"))
      (node (ref "U5") (pin "9") (pinfunction "EP_9") (pintype "unspecified"))
      (node (ref "U6") (pin "1") (pinfunction "1_1") (pintype "unspecified"))
      (node (ref "U6") (pin "33") (pinfunction "33_33") (pintype "unspecified"))
      (node (ref "U6") (pin "39") (pinfunction "39_39") (pintype "unspecified"))
      (node (ref "U6") (pin "45") (pinfunction "45_45") (pintype "unspecified"))
      (node (ref "U6") (pin "51") (pinfunction "51_51") (pintype "unspecified"))
      (node (ref "U6") (pin "57") (pinfunction "57_57") (pintype "unspecified"))
      (node (ref "U6") (pin "63") (pinfunction "63_63") (pintype "unspecified"))
      (node (ref "U6") (pin "69") (pinfunction "69_69") (pintype "unspecified"))
      (node (ref "U6") (pin "7") (pinfunction "7_7") (pintype "unspecified"))
      (node (ref "U6") (pin "75") (pinfunction "75_75") (pintype "unspecified"))
      (node (ref "U6") (pin "76") (pinfunction "76_76") (pintype "unspecified"))
      (node (ref "U6") (pin "77") (pinfunction "77_77") (pintype "unspecified"))
      (node (ref "U7") (pin "1") (pinfunction "1_1") (pintype "unspecified"))
      (node (ref "U7") (pin "15") (pinfunction "15_15") (pintype "unspecified"))
      (node (ref "U7") (pin "21") (pinfunction "21_21") (pintype "unspecified"))
      (node (ref "U7") (pin "27") (pinfunction "27_27") (pintype "unspecified"))
      (node (ref "U7") (pin "3") (pinfunction "3_3") (pintype "unspecified"))
      (node (ref "U7") (pin "33") (pinfunction "33_33") (pintype "unspecified"))
      (node (ref "U7") (pin "39") (pinfunction "39_39") (pintype "unspecified"))
      (node (ref "U7") (pin "45") (pinfunction "45_45") (pintype "unspecified"))
      (node (ref "U7") (pin "51") (pinfunction "51_51") (pintype "unspecified"))
      (node (ref "U7") (pin "57") (pinfunction "57_57") (pintype "unspecified"))
      (node (ref "U7") (pin "71") (pinfunction "71_71") (pintype "unspecified"))
      (node (ref "U7") (pin "73") (pinfunction "73_73") (pintype "unspecified"))
      (node (ref "U7") (pin "75") (pinfunction "75_75") (pintype "unspecified"))
      (node (ref "U7") (pin "76") (pinfunction "76_76") (pintype "unspecified"))
      (node (ref "U7") (pin "77") (pinfunction "77_77") (pintype "unspecified"))
      (node (ref "U7") (pin "9") (pinfunction "9_9") (pintype "unspecified"))
      (node (ref "U8") (pin "40") (pinfunction "GND_40") (pintype "unspecified"))
      (node (ref "U8") (pin "49") (pinfunction "GND_49") (pintype "unspecified"))
      (node (ref "U9") (pin "2") (pinfunction "GND_2") (pintype "unspecified"))
      (node (ref "USB1") (pin "10") (pinfunction "GND_10") (pintype "unspecified"))
      (node (ref "USB1") (pin "11") (pinfunction "GND_11") (pintype "unspecified"))
      (node (ref "USB1") (pin "12") (pinfunction "GND_12") (pintype "unspecified"))
      (node (ref "USB1") (pin "4") (pinfunction "GND_4") (pintype "unspecified"))
      (node (ref "USB1") (pin "8") (pinfunction "GND_8") (pintype "unspecified"))
      (node (ref "USB1") (pin "9") (pinfunction "GND_9") (pintype "unspecified"))
      (node (ref "USB2") (pin "10") (pinfunction "GND_10") (pintype "unspecified"))
      (node (ref "USB2") (pin "11") (pinfunction "GND_11") (pintype "unspecified"))
      (node (ref "USB2") (pin "12") (pinfunction "GND_12") (pintype "unspecified"))
      (node (ref "USB2") (pin "4") (pinfunction "GND_4") (pintype "unspecified"))
      (node (ref "USB2") (pin "8") (pinfunction "GND_8") (pintype "unspecified"))
      (node (ref "USB2") (pin "9") (pinfunction "GND_9") (pintype "unspecified"))
    )
    (net (code "25") (name "ETH_TX_N") (class "Default")
      (node (ref "U8") (pin "42") (pinfunction "HSIN_42") (pintype "unspecified"))
    )
    (net (code "26") (name "ETH_TX_P") (class "Default")
      (node (ref "U8") (pin "41") (pinfunction "HSIP_41") (pintype "unspecified"))
    )
    (net (code "27") (name "ETH_WAKE_N") (class "Default")
      (node (ref "R19") (pin "2") (pinfunction "2_2") (pintype "unspecified"))
      (node (ref "U8") (pin "2") (pinfunction "LANWAKEB_2") (pintype "unspecified"))
    )
    (net (code "28") (name "LED0") (class "Default")
      (node (ref "R21") (pin "2") (pinfunction "2_2") (pintype "input"))
      (node (ref "U8") (pin "30") (pinfunction "LED0/EEDI/SPISI/SDA_30") (pintype "unspecified"))
    )
    (net (code "29") (name "LED2") (class "Default")
      (node (ref "R20") (pin "1") (pinfunction "1_1") (pintype "input"))
      (node (ref "U8") (pin "25") (pinfunction "LED2/EEDO/SPIS0_25") (pintype "unspecified"))
    )
    (net (code "30") (name "NVME_CLKREQ_N") (class "Default")
      (node (ref "R15") (pin "1") (pinfunction "1_1") (pintype "unspecified"))
      (node (ref "U7") (pin "52") (pinfunction "52_52") (pintype "unspecified"))
    )
    (net (code "31") (name "NVME_CLK_N") (class "Default")
      (node (ref "U7") (pin "53") (pinfunction "53_53") (pintype "unspecified"))
    )
    (net (code "32") (name "NVME_CLK_P") (class "Default")
      (node (ref "U7") (pin "55") (pinfunction "55_55") (pintype "unspecified"))
    )
    (net (code "33") (name "NVME_RST_N") (class "Default")
      (node (ref "C43") (pin "1") (pinfunction "1_1") (pintype "unspecified"))
      (node (ref "R14") (pin "1") (pinfunction "1_1") (pintype "unspecified"))
      (node (ref "U7") (pin "50") (pinfunction "50_50") (pintype "unspecified"))
    )
    (net (code "34") (name "NVME_RX0_N") (class "Default")
      (node (ref "U7") (pin "47") (pinfunction "47_47") (pintype "unspecified"))
    )
    (net (code "35") (name "NVME_RX0_P") (class "Default")
      (node (ref "U7") (pin "49") (pinfunction "49_49") (pintype "unspecified"))
    )
    (net (code "36") (name "NVME_RX1_N") (class "Default")
      (node (ref "U7") (pin "35") (pinfunction "35_35") (pintype "unspecified"))
    )
    (net (code "37") (name "NVME_RX1_P") (class "Default")
      (node (ref "U7") (pin "37") (pinfunction "37_37") (pintype "unspecified"))
    )
    (net (code "38") (name "NVME_RX2_N") (class "Default")
      (node (ref "U7") (pin "23") (pinfunction "23_23") (pintype "unspecified"))
    )
    (net (code "39") (name "NVME_RX2_P") (class "Default")
      (node (ref "U7") (pin "25") (pinfunction "25_25") (pintype "unspecified"))
    )
    (net (code "40") (name "NVME_RX3_N") (class "Default")
      (node (ref "U7") (pin "11") (pinfunction "11_11") (pintype "unspecified"))
    )
    (net (code "41") (name "NVME_RX3_P") (class "Default")
      (node (ref "U7") (pin "13") (pinfunction "13_13") (pintype "unspecified"))
    )
    (net (code "42") (name "NVME_TX0_N") (class "Default")
      (node (ref "C50") (pin "1") (pinfunction "1_1") (pintype "unspecified"))
    )
    (net (code "43") (name "NVME_TX0_P") (class "Default")
      (node (ref "C51") (pin "1") (pinfunction "1_1") (pintype "unspecified"))
    )
    (net (code "44") (name "NVME_TX1_N") (class "Default")
      (node (ref "C48") (pin "1") (pinfunction "1_1") (pintype "unspecified"))
    )
    (net (code "45") (name "NVME_TX1_P") (class "Default")
      (node (ref "C49") (pin "1") (pinfunction "1_1") (pintype "unspecified"))
    )
    (net (code "46") (name "NVME_TX2_N") (class "Default")
      (node (ref "C46") (pin "1") (pinfunction "1_1") (pintype "unspecified"))
    )
    (net (code "47") (name "NVME_TX2_P") (class "Default")
      (node (ref "C47") (pin "1") (pinfunction "1_1") (pintype "unspecified"))
    )
    (net (code "48") (name "NVME_TX3_N") (class "Default")
      (node (ref "C44") (pin "1") (pinfunction "1_1") (pintype "unspecified"))
    )
    (net (code "49") (name "NVME_TX3_P") (class "Default")
      (node (ref "C45") (pin "1") (pinfunction "1_1") (pintype "unspecified"))
    )
    (net (code "50") (name "NVME_WAKE_N") (class "Default")
      (node (ref "R16") (pin "1") (pinfunction "1_1") (pintype "unspecified"))
      (node (ref "U7") (pin "54") (pinfunction "54_54") (pintype "unspecified"))
    )
    (net (code "51") (name "Net-(C1-Pad1)") (class "Default")
      (node (ref "C1") (pin "1") (pinfunction "1_1") (pintype "unspecified"))
      (node (ref "R2") (pin "2") (pinfunction "2_2") (pintype "unspecified"))
    )
    (net (code "52") (name "Net-(C8-Pad1)") (class "Default")
      (node (ref "C8") (pin "1") (pinfunction "1_1") (pintype "unspecified"))
      (node (ref "R5") (pin "2") (pinfunction "2_2") (pintype "input"))
    )
    (net (code "53") (name "Net-(C33-Pad1)") (class "Default")
      (node (ref "C33") (pin "1") (pinfunction "1_1") (pintype "unspecified"))
      (node (ref "U6") (pin "41") (pinfunction "41_41") (pintype "unspecified"))
    )
    (net (code "54") (name "Net-(C34-Pad1)") (class "Default")
      (node (ref "C34") (pin "1") (pinfunction "1_1") (pintype "unspecified"))
      (node (ref "U6") (pin "43") (pinfunction "43_43") (pintype "unspecified"))
    )
    (net (code "55") (name "Net-(C38-Pad1)") (class "Default")
      (node (ref "C38") (pin "1") (pinfunction "1_1") (pintype "input"))
      (node (ref "U7") (pin "2") (pinfunction "2_2") (pintype "unspecified"))
    )
    (net (code "56") (name "Net-(C39-Pad1)") (class "Default")
      (node (ref "C39") (pin "1") (pinfunction "1_1") (pintype "input"))
      (node (ref "U7") (pin "4") (pinfunction "4_4") (pintype "unspecified"))
    )
    (net (code "57") (name "Net-(C40-Pad1)") (class "Default")
      (node (ref "C40") (pin "1") (pinfunction "1_1") (pintype "input"))
      (node (ref "U7") (pin "70") (pinfunction "70_70") (pintype "unspecified"))
    )
    (net (code "58") (name "Net-(C41-Pad1)") (class "Default")
      (node (ref "C41") (pin "1") (pinfunction "1_1") (pintype "input"))
      (node (ref "U7") (pin "72") (pinfunction "72_72") (pintype "unspecified"))
    )
    (net (code "59") (name "Net-(C42-Pad1)") (class "Default")
      (node (ref "C42") (pin "1") (pinfunction "1_1") (pintype "input"))
      (node (ref "U7") (pin "74") (pinfunction "74_74") (pintype "unspecified"))
    )
    (net (code "60") (name "Net-(C44-Pad2)") (class "Default")
      (node (ref "C44") (pin "2") (pinfunction "2_2") (pintype "unspecified"))
      (node (ref "U7") (pin "5") (pinfunction "5_5") (pintype "unspecified"))
    )
    (net (code "61") (name "Net-(C45-Pad2)") (class "Default")
      (node (ref "C45") (pin "2") (pinfunction "2_2") (pintype "unspecified"))
      (node (ref "U7") (pin "7") (pinfunction "7_7") (pintype "unspecified"))
    )
    (net (code "62") (name "Net-(C46-Pad2)") (class "Default")
      (node (ref "C46") (pin "2") (pinfunction "2_2") (pintype "unspecified"))
      (node (ref "U7") (pin "17") (pinfunction "17_17") (pintype "unspecified"))
    )
    (net (code "63") (name "Net-(C47-Pad2)") (class "Default")
      (node (ref "C47") (pin "2") (pinfunction "2_2") (pintype "unspecified"))
      (node (ref "U7") (pin "19") (pinfunction "19_19") (pintype "unspecified"))
    )
    (net (code "64") (name "Net-(C48-Pad2)") (class "Default")
      (node (ref "C48") (pin "2") (pinfunction "2_2") (pintype "unspecified"))
      (node (ref "U7") (pin "29") (pinfunction "29_29") (pintype "unspecified"))
    )
    (net (code "65") (name "Net-(C49-Pad2)") (class "Default")
      (node (ref "C49") (pin "2") (pinfunction "2_2") (pintype "unspecified"))
      (node (ref "U7") (pin "31") (pinfunction "31_31") (pintype "unspecified"))
    )
    (net (code "66") (name "Net-(C50-Pad2)") (class "Default")
      (node (ref "C50") (pin "2") (pinfunction "2_2") (pintype "unspecified"))
      (node (ref "U7") (pin "41") (pinfunction "41_41") (pintype "unspecified"))
    )
    (net (code "67") (name "Net-(C51-Pad2)") (class "Default")
      (node (ref "C51") (pin "2") (pinfunction "2_2") (pintype "unspecified"))
      (node (ref "U7") (pin "43") (pinfunction "43_43") (pintype "unspecified"))
    )
    (net (code "68") (name "Net-(C93-Pad1)") (class "Default")
      (node (ref "C93") (pin "1") (pinfunction "1_1") (pintype "unspecified"))
      (node (ref "U10") (pin "46") (pinfunction "VDD10_46") (pintype "unspecified"))
    )
    (net (code "69") (name "Net-(CN1-P7)") (class "Default")
      (node (ref "C15") (pin "1") (pinfunction "1_1") (pintype "unspecified"))
      (node (ref "CN1") (pin "14") (pinfunction "P7_14") (pintype "unspecified"))
    )
    (net (code "70") (name "Net-(CN1-P8)") (class "Default")
      (node (ref "C14") (pin "1") (pinfunction "1_1") (pintype "unspecified"))
      (node (ref "CN1") (pin "15") (pinfunction "P8_15") (pintype "unspecified"))
    )
    (net (code "71") (name "Net-(CN1-P9)") (class "Default")
      (node (ref "C13") (pin "1") (pinfunction "1_1") (pintype "unspecified"))
      (node (ref "CN1") (pin "16") (pinfunction "P9_16") (pintype "unspecified"))
    )
    (net (code "72") (name "Net-(CN1-S2)") (class "Default")
      (node (ref "C19") (pin "1") (pinfunction "1_1") (pintype "unspecified"))
      (node (ref "CN1") (pin "2") (pinfunction "S2_2") (pintype "unspecified"))
    )
    (net (code "73") (name "Net-(CN1-S3)") (class "Default")
      (node (ref "C18") (pin "1") (pinfunction "1_1") (pintype "unspecified"))
      (node (ref "CN1") (pin "3") (pinfunction "S3_3") (pintype "unspecified"))
    )
    (net (code "74") (name "Net-(CN1-S5)") (class "Default")
      (node (ref "C17") (pin "1") (pinfunction "1_1") (pintype "unspecified"))
      (node (ref "CN1") (pin "5") (pinfunction "S5_5") (pintype "unspecified"))
    )
    (net (code "75") (name "Net-(CN1-S6)") (class "Default")
      (node (ref "C16") (pin "1") (pinfunction "1_1") (pintype "unspecified"))
      (node (ref "CN1") (pin "6") (pinfunction "S6_6") (pintype "unspecified"))
    )
    (net (code "76") (name "Net-(CN2-P7)") (class "Default")
      (node (ref "C24") (pin "1") (pinfunction "1_1") (pintype "unspecified"))
      (node (ref "CN2") (pin "14") (pinfunction "P7_14") (pintype "unspecified"))
    )
    (net (code "77") (name "Net-(CN2-P8)") (class "Default")
      (node (ref "C25") (pin "1") (pinfunction "1_1") (pintype "unspecified"))
      (node (ref "CN2") (pin "15") (pinfunction "P8_15") (pintype "unspecified"))
    )
    (net (code "78") (name "Net-(CN2-P9)") (class "Default")
      (node (ref "C26") (pin "1") (pinfunction "1_1") (pintype "unspecified"))
      (node (ref "CN2") (pin "16") (pinfunction "P9_16") (pintype "unspecified"))
    )
    (net (code "79") (name "Net-(CN2-S2)") (class "Default")
      (node (ref "C23") (pin "1") (pinfunction "1_1") (pintype "unspecified"))
      (node (ref "CN2") (pin "2") (pinfunction "S2_2") (pintype "unspecified"))
    )
    (net (code "80") (name "Net-(CN2-S3)") (class "Default")
      (node (ref "C22") (pin "1") (pinfunction "1_1") (pintype "unspecified"))
      (node (ref "CN2") (pin "3") (pinfunction "S3_3") (pintype "unspecified"))
    )
    (net (code "81") (name "Net-(CN2-S5)") (class "Default")
      (node (ref "C21") (pin "1") (pinfunction "1_1") (pintype "unspecified"))
      (node (ref "CN2") (pin "5") (pinfunction "S5_5") (pintype "unspecified"))
    )
    (net (code "82") (name "Net-(CN2-S6)") (class "Default")
      (node (ref "C20") (pin "1") (pinfunction "1_1") (pintype "unspecified"))
      (node (ref "CN2") (pin "6") (pinfunction "S6_6") (pintype "unspecified"))
    )
    (net (code "83") (name "Net-(D1-Pad4)") (class "Default")
      (node (ref "D1") (pin "4") (pinfunction "4_4") (pintype "input"))
      (node (ref "USB1") (pin "2") (pinfunction "D-_2") (pintype "unspecified"))
    )
    (net (code "84") (name "Net-(D1-Pad6)") (class "Default")
      (node (ref "D1") (pin "6") (pinfunction "6_6") (pintype "input"))
      (node (ref "USB1") (pin "3") (pinfunction "D+_3") (pintype "unspecified"))
    )
    (net (code "85") (name "Net-(D3-Pad4)") (class "Default")
      (node (ref "D3") (pin "4") (pinfunction "4_4") (pintype "input"))
      (node (ref "USB1") (pin "6") (pinfunction "D-_6") (pintype "unspecified"))
    )
    (net (code "86") (name "Net-(D3-Pad6)") (class "Default")
      (node (ref "D3") (pin "6") (pinfunction "6_6") (pintype "input"))
      (node (ref "USB1") (pin "7") (pinfunction "D+_7") (pintype "unspecified"))
    )
    (net (code "87") (name "Net-(D4-Pad4)") (class "Default")
      (node (ref "D4") (pin "4") (pinfunction "4_4") (pintype "input"))
      (node (ref "USB2") (pin "2") (pinfunction "D-_2") (pintype "unspecified"))
    )
    (net (code "88") (name "Net-(D4-Pad6)") (class "Default")
      (node (ref "D4") (pin "6") (pinfunction "6_6") (pintype "input"))
      (node (ref "USB2") (pin "3") (pinfunction "D+_3") (pintype "unspecified"))
    )
    (net (code "89") (name "Net-(D5-Pad4)") (class "Default")
      (node (ref "D5") (pin "4") (pinfunction "4_4") (pintype "input"))
      (node (ref "USB2") (pin "6") (pinfunction "D-_6") (pintype "unspecified"))
    )
    (net (code "90") (name "Net-(D5-Pad6)") (class "Default")
      (node (ref "D5") (pin "6") (pinfunction "6_6") (pintype "input"))
      (node (ref "USB2") (pin "7") (pinfunction "D+_7") (pintype "unspecified"))
    )
    (net (code "91") (name "Net-(RJ1-LED_G-O+)") (class "Default")
      (node (ref "R20") (pin "2") (pinfunction "2_2") (pintype "input"))
      (node (ref "RJ1") (pin "L1") (pinfunction "LED_G-O+_L1") (pintype "unspecified"))
    )
    (net (code "92") (name "Net-(RJ1-LED_Y-)") (class "Default")
      (node (ref "R21") (pin "1") (pinfunction "1_1") (pintype "input"))
      (node (ref "RJ1") (pin "L3") (pinfunction "LED_Y-_L3") (pintype "unspecified"))
    )
    (net (code "93") (name "Net-(U1-BST)") (class "Default")
      (node (ref "C2") (pin "1") (pinfunction "1_1") (pintype "unspecified"))
      (node (ref "U1") (pin "1") (pinfunction "BST_1") (pintype "unspecified"))
    )
    (net (code "94") (name "Net-(U1-COMP)") (class "Default")
      (node (ref "R2") (pin "1") (pinfunction "1_1") (pintype "unspecified"))
      (node (ref "U1") (pin "6") (pinfunction "COMP_6") (pintype "unspecified"))
    )
    (net (code "95") (name "Net-(U1-EN)") (class "Default")
      (node (ref "R1") (pin "2") (pinfunction "2_2") (pintype "unspecified"))
      (node (ref "U1") (pin "3") (pinfunction "EN_3") (pintype "unspecified"))
    )
    (net (code "96") (name "Net-(U1-FB)") (class "Default")
      (node (ref "R3") (pin "2") (pinfunction "2_2") (pintype "unspecified"))
      (node (ref "R4") (pin "2") (pinfunction "2_2") (pintype "unspecified"))
      (node (ref "U1") (pin "5") (pinfunction "FB_5") (pintype "unspecified"))
    )
    (net (code "97") (name "Net-(U1-RT{slash}CLK)") (class "Default")
      (node (ref "R6") (pin "2") (pinfunction "2_2") (pintype "unspecified"))
      (node (ref "U1") (pin "4") (pinfunction "RT/CLK_4") (pintype "unspecified"))
    )
    (net (code "98") (name "Net-(U1-SW)") (class "Default")
      (node (ref "C2") (pin "2") (pinfunction "2_2") (pintype "unspecified"))
      (node (ref "U1") (pin "8") (pinfunction "SW_8") (pintype "unspecified"))
      (node (ref "U2") (pin "1") (pinfunction "1_1") (pintype "unspecified"))
    )
    (net (code "99") (name "Net-(U5-BST)") (class "Default")
      (node (ref "C7") (pin "1") (pinfunction "1_1") (pintype "unspecified"))
      (node (ref "U5") (pin "1") (pinfunction "BST_1") (pintype "unspecified"))
    )
    (net (code "100") (name "Net-(U5-COMP)") (class "Default")
      (node (ref "R5") (pin "1") (pinfunction "1_1") (pintype "input"))
      (node (ref "U5") (pin "6") (pinfunction "COMP_6") (pintype "unspecified"))
    )
    (net (code "101") (name "Net-(U5-EN)") (class "Default")
      (node (ref "R11") (pin "2") (pinfunction "2_2") (pintype "unspecified"))
      (node (ref "U5") (pin "3") (pinfunction "EN_3") (pintype "unspecified"))
    )
    (net (code "102") (name "Net-(U5-FB)") (class "Default")
      (node (ref "R8") (pin "2") (pinfunction "2_2") (pintype "unspecified"))
      (node (ref "U3") (pin "1") (pinfunction "1_1") (pintype "unspecified"))
      (node (ref "U5") (pin "5") (pinfunction "FB_5") (pintype "unspecified"))
    )
    (net (code "103") (name "Net-(U5-RT{slash}CLK)") (class "Default")
      (node (ref "R7") (pin "2") (pinfunction "2_2") (pintype "unspecified"))
      (node (ref "U5") (pin "4") (pinfunction "RT/CLK_4") (pintype "unspecified"))
    )
    (net (code "104") (name "Net-(U5-SW)") (class "Default")
      (node (ref "C7") (pin "2") (pinfunction "2_2") (pintype "unspecified"))
      (node (ref "U4") (pin "1") (pinfunction "1_1") (pintype "unspecified"))
      (node (ref "U5") (pin "8") (pinfunction "SW_8") (pintype "unspecified"))
    )
    (net (code "105") (name "Net-(U8-HSON)") (class "Default")
      (node (ref "C56") (pin "1") (pinfunction "1_1") (pintype "unspecified"))
      (node (ref "U8") (pin "39") (pinfunction "HSON_39") (pintype "unspecified"))
    )
    (net (code "106") (name "Net-(U8-HSOP)") (class "Default")
      (node (ref "C57") (pin "1") (pinfunction "1_1") (pintype "unspecified"))
      (node (ref "U8") (pin "38") (pinfunction "HSOP_38") (pintype "unspecified"))
    )
    (net (code "107") (name "Net-(U8-ISOLATEB)") (class "Default")
      (node (ref "R18") (pin "1") (pinfunction "1_1") (pintype "input"))
      (node (ref "U8") (pin "1") (pinfunction "ISOLATEB_1") (pintype "unspecified"))
    )
    (net (code "108") (name "Net-(U8-LED1{slash}EESK{slash}SPISC)") (class "Default")
      (node (ref "R22") (pin "1") (pinfunction "1_1") (pintype "input"))
      (node (ref "U8") (pin "27") (pinfunction "LED1/EESK/SPISC_27") (pintype "unspecified"))
    )
    (net (code "109") (name "Net-(U8-RSET)") (class "Default")
      (node (ref "R23") (pin "2") (pinfunction "2_2") (pintype "unspecified"))
      (node (ref "U8") (pin "12") (pinfunction "RSET_12") (pintype "unspecified"))
    )
    (net (code "110") (name "Net-(U9-FB)") (class "Default")
      (node (ref "R24") (pin "1") (pinfunction "1_1") (pintype "unspecified"))
      (node (ref "R25") (pin "1") (pinfunction "1_1") (pintype "unspecified"))
      (node (ref "U9") (pin "1") (pinfunction "FB_1") (pintype "unspecified"))
    )
    (net (code "111") (name "Net-(U9-SW)") (class "Default")
      (node (ref "L3") (pin "1") (pinfunction "1_1") (pintype "unspecified"))
      (node (ref "U9") (pin "4") (pinfunction "SW_4") (pintype "unspecified"))
    )
    (net (code "112") (name "Net-(U10-PETXN)") (class "Default")
      (node (ref "C84") (pin "2") (pinfunction "2_2") (pintype "unspecified"))
      (node (ref "U10") (pin "8") (pinfunction "PETXN_8") (pintype "unspecified"))
    )
    (net (code "113") (name "Net-(U10-PETXP)") (class "Default")
      (node (ref "C83") (pin "2") (pinfunction "2_2") (pintype "unspecified"))
      (node (ref "U10") (pin "7") (pinfunction "PETXP_7") (pintype "unspecified"))
    )
    (net (code "114") (name "Net-(U10-RREF)") (class "Default")
      (node (ref "R33") (pin "1") (pinfunction "1_1") (pintype "unspecified"))
      (node (ref "U10") (pin "33") (pinfunction "RREF_33") (pintype "unspecified"))
    )
    (net (code "115") (name "Net-(U10-SMIB)") (class "Default")
      (node (ref "R32") (pin "1") (pinfunction "1_1") (pintype "unspecified"))
      (node (ref "U10") (pin "1") (pinfunction "SMIB_1") (pintype "unspecified"))
    )
    (net (code "116") (name "Net-(U10-SPICSB)") (class "Default")
      (node (ref "R35") (pin "1") (pinfunction "1_1") (pintype "unspecified"))
      (node (ref "U10") (pin "17") (pinfunction "SPICSB_17") (pintype "unspecified"))
      (node (ref "U16") (pin "1") (pinfunction "CS#_1") (pintype "unspecified"))
    )
    (net (code "117") (name "Net-(U10-SPISCK)") (class "Default")
      (node (ref "R36") (pin "1") (pinfunction "1_1") (pintype "unspecified"))
      (node (ref "U10") (pin "18") (pinfunction "SPISCK_18") (pintype "unspecified"))
      (node (ref "U16") (pin "6") (pinfunction "CLK_6") (pintype "unspecified"))
    )
    (net (code "118") (name "Net-(U10-SPISI)") (class "Default")
      (node (ref "R37") (pin "1") (pinfunction "1_1") (pintype "unspecified"))
      (node (ref "U10") (pin "19") (pinfunction "SPISI_19") (pintype "unspecified"))
      (node (ref "U16") (pin "5") (pinfunction "DI(IO0)_5") (pintype "unspecified"))
    )
    (net (code "119") (name "Net-(U10-SPISO)") (class "Default")
      (node (ref "R34") (pin "1") (pinfunction "1_1") (pintype "unspecified"))
      (node (ref "U10") (pin "16") (pinfunction "SPISO_16") (pintype "unspecified"))
      (node (ref "U16") (pin "2") (pinfunction "DO(IO1)_2") (pintype "unspecified"))
    )
    (net (code "120") (name "Net-(U10-U3TXDN1)") (class "Default")
      (node (ref "C105") (pin "1") (pinfunction "1_1") (pintype "unspecified"))
      (node (ref "U10") (pin "36") (pinfunction "U3TXDN1_36") (pintype "unspecified"))
    )
    (net (code "121") (name "Net-(U10-U3TXDN2)") (class "Default")
      (node (ref "C108") (pin "1") (pinfunction "1_1") (pintype "unspecified"))
      (node (ref "U10") (pin "45") (pinfunction "U3TXDN2_45") (pintype "unspecified"))
    )
    (net (code "122") (name "Net-(U10-U3TXDP1)") (class "Default")
      (node (ref "C106") (pin "1") (pinfunction "1_1") (pintype "unspecified"))
      (node (ref "U10") (pin "35") (pinfunction "U3TXDP1_35") (pintype "unspecified"))
    )
    (net (code "123") (name "Net-(U10-U3TXDP2)") (class "Default")
      (node (ref "C107") (pin "1") (pinfunction "1_1") (pintype "unspecified"))
      (node (ref "U10") (pin "44") (pinfunction "U3TXDP2_44") (pintype "unspecified"))
    )
    (net (code "124") (name "Net-(U10-XT1)") (class "Default")
      (node (ref "C86") (pin "2") (pinfunction "2_2") (pintype "unspecified"))
      (node (ref "U10") (pin "31") (pinfunction "XT1_31") (pintype "unspecified"))
      (node (ref "X2") (pin "2") (pinfunction "OSC2_2") (pintype "input"))
    )
    (net (code "125") (name "Net-(U10-XT2)") (class "Default")
      (node (ref "C85") (pin "2") (pinfunction "2_2") (pintype "unspecified"))
      (node (ref "U10") (pin "30") (pinfunction "XT2_30") (pintype "unspecified"))
      (node (ref "X2") (pin "1") (pinfunction "OSC1_1") (pintype "input"))
    )
    (net (code "126") (name "Net-(U11-D+)") (class "Default")
      (node (ref "D6") (pin "3") (pinfunction "3_3") (pintype "input"))
      (node (ref "U11") (pin "3") (pinfunction "D+_3") (pintype "unspecified"))
    )
    (net (code "127") (name "Net-(U11-D-)") (class "Default")
      (node (ref "D6") (pin "1") (pinfunction "1_1") (pintype "input"))
      (node (ref "U11") (pin "2") (pinfunction "D-_2") (pintype "unspecified"))
    )
    (net (code "128") (name "Net-(U11-GND)") (class "Default")
      (node (ref "D2") (pin "2") (pinfunction "2_2") (pintype "input"))
      (node (ref "D6") (pin "2") (pinfunction "2_2") (pintype "input"))
      (node (ref "U11") (pin "10") (pinfunction "EH_10") (pintype "unspecified"))
      (node (ref "U11") (pin "11") (pinfunction "EH_11") (pintype "unspecified"))
      (node (ref "U11") (pin "4") (pinfunction "GND_4") (pintype "unspecified"))
      (node (ref "U11") (pin "7") (pinfunction "GND_DRAIN_7") (pintype "unspecified"))
    )
    (net (code "129") (name "Net-(U11-VBUS)") (class "Default")
      (node (ref "D2") (pin "5") (pinfunction "5_5") (pintype "input"))
      (node (ref "D6") (pin "5") (pinfunction "5_5") (pintype "input"))
      (node (ref "U11") (pin "1") (pinfunction "VBUS_1") (pintype "unspecified"))
      (node (ref "U13") (pin "7") (pinfunction "OUT1_7") (pintype "unspecified"))
    )
    (net (code "130") (name "Net-(U12-D+)") (class "Default")
      (node (ref "D7") (pin "3") (pinfunction "3_3") (pintype "input"))
      (node (ref "U12") (pin "3") (pinfunction "D+_3") (pintype "unspecified"))
    )
    (net (code "131") (name "Net-(U12-D-)") (class "Default")
      (node (ref "D7") (pin "1") (pinfunction "1_1") (pintype "input"))
      (node (ref "U12") (pin "2") (pinfunction "D-_2") (pintype "unspecified"))
    )
    (net (code "132") (name "Net-(U12-GND)") (class "Default")
      (node (ref "D7") (pin "2") (pinfunction "2_2") (pintype "input"))
      (node (ref "D8") (pin "2") (pinfunction "2_2") (pintype "input"))
      (node (ref "U12") (pin "10") (pinfunction "EH_10") (pintype "unspecified"))
      (node (ref "U12") (pin "11") (pinfunction "EH_11") (pintype "unspecified"))
      (node (ref "U12") (pin "4") (pinfunction "GND_4") (pintype "unspecified"))
      (node (ref "U12") (pin "7") (pinfunction "GND_DRAIN_7") (pintype "unspecified"))
    )
    (net (code "133") (name "Net-(U12-VBUS)") (class "Default")
      (node (ref "D7") (pin "5") (pinfunction "5_5") (pintype "input"))
      (node (ref "D8") (pin "5") (pinfunction "5_5") (pintype "input"))
      (node (ref "U12") (pin "1") (pinfunction "VBUS_1") (pintype "unspecified"))
      (node (ref "U13") (pin "6") (pinfunction "OUT2_6") (pintype "unspecified"))
    )
    (net (code "134") (name "Net-(U14-EN1#†)") (class "Default")
      (node (ref "R28") (pin "2") (pinfunction "2_2") (pintype "unspecified"))
      (node (ref "U14") (pin "3") (pinfunction "EN1#†_3") (pintype "input"))
      (node (ref "U14") (pin "4") (pinfunction "EN2#†_4") (pintype "input"))
    )
    (net (code "135") (name "Net-(U14-OC1#)") (class "Default")
      (node (ref "R26") (pin "1") (pinfunction "1_1") (pintype "unspecified"))
      (node (ref "U14") (pin "8") (pinfunction "OC1#_8") (pintype "output"))
    )
    (net (code "136") (name "Net-(U14-OC2#)") (class "Default")
      (node (ref "R27") (pin "1") (pinfunction "1_1") (pintype "unspecified"))
      (node (ref "U14") (pin "5") (pinfunction "OC2#_5") (pintype "output"))
    )
    (net (code "137") (name "Net-(U15-EN1#†)") (class "Default")
      (node (ref "R29") (pin "2") (pinfunction "2_2") (pintype "unspecified"))
      (node (ref "U15") (pin "3") (pinfunction "EN1#†_3") (pintype "input"))
      (node (ref "U15") (pin "4") (pinfunction "EN2#†_4") (pintype "input"))
    )
    (net (code "138") (name "Net-(U15-OC1#)") (class "Default")
      (node (ref "R30") (pin "1") (pinfunction "1_1") (pintype "unspecified"))
      (node (ref "U15") (pin "8") (pinfunction "OC1#_8") (pintype "output"))
    )
    (net (code "139") (name "Net-(U15-OC2#)") (class "Default")
      (node (ref "R31") (pin "1") (pinfunction "1_1") (pintype "unspecified"))
      (node (ref "U15") (pin "5") (pinfunction "OC2#_5") (pintype "output"))
    )
    (net (code "140") (name "Net-(U16-HOLD#(IO3))") (class "Default")
      (node (ref "R41") (pin "1") (pinfunction "1_1") (pintype "unspecified"))
      (node (ref "U16") (pin "7") (pinfunction "HOLD#(IO3)_7") (pintype "unspecified"))
    )
    (net (code "141") (name "Net-(U16-WP#(IO2))") (class "Default")
      (node (ref "R42") (pin "1") (pinfunction "1_1") (pintype "unspecified"))
      (node (ref "U16") (pin "3") (pinfunction "WP#(IO2)_3") (pintype "unspecified"))
    )
    (net (code "142") (name "Net-(U17-FB)") (class "Default")
      (node (ref "R38") (pin "1") (pinfunction "1_1") (pintype "unspecified"))
      (node (ref "R39") (pin "1") (pinfunction "1_1") (pintype "input"))
      (node (ref "U17") (pin "1") (pinfunction "FB_1") (pintype "unspecified"))
    )
    (net (code "143") (name "Net-(U17-SW)") (class "Default")
      (node (ref "L4") (pin "1") (pinfunction "1_1") (pintype "unspecified"))
      (node (ref "U17") (pin "4") (pinfunction "SW_4") (pintype "unspecified"))
    )
    (net (code "144") (name "Net-(X1-GND)") (class "Default")
      (node (ref "C52") (pin "1") (pinfunction "1_1") (pintype "unspecified"))
      (node (ref "X1") (pin "2") (pinfunction "GND_2") (pintype "unspecified"))
    )
    (net (code "145") (name "POWEXT") (class "Default")
      (node (ref "U8") (pin "6") (pinfunction "POW_EXT_SWR_6") (pintype "unspecified"))
      (node (ref "U9") (pin "5") (pinfunction "EN_5") (pintype "unspecified"))
    )
    (net (code "146") (name "SATA0_RX_N") (class "Default")
      (node (ref "C17") (pin "2") (pinfunction "2_2") (pintype "unspecified"))
    )
    (net (code "147") (name "SATA0_RX_P") (class "Default")
      (node (ref "C16") (pin "2") (pinfunction "2_2") (pintype "unspecified"))
    )
    (net (code "148") (name "SATA0_TX_N") (class "Default")
      (node (ref "C18") (pin "2") (pinfunction "2_2") (pintype "unspecified"))
    )
    (net (code "149") (name "SATA0_TX_P") (class "Default")
      (node (ref "C19") (pin "2") (pinfunction "2_2") (pintype "unspecified"))
    )
    (net (code "150") (name "SATA1_RX_N") (class "Default")
      (node (ref "C21") (pin "2") (pinfunction "2_2") (pintype "unspecified"))
    )
    (net (code "151") (name "SATA1_RX_P") (class "Default")
      (node (ref "C20") (pin "2") (pinfunction "2_2") (pintype "unspecified"))
    )
    (net (code "152") (name "SATA1_TX_N") (class "Default")
      (node (ref "C22") (pin "2") (pinfunction "2_2") (pintype "unspecified"))
    )
    (net (code "153") (name "SATA1_TX_P") (class "Default")
      (node (ref "C23") (pin "2") (pinfunction "2_2") (pintype "unspecified"))
    )
    (net (code "154") (name "USB1N") (class "Default")
      (node (ref "D1") (pin "3") (pinfunction "3_3") (pintype "input"))
    )
    (net (code "155") (name "USB1P") (class "Default")
      (node (ref "D1") (pin "1") (pinfunction "1_1") (pintype "input"))
    )
    (net (code "156") (name "USB2N") (class "Default")
      (node (ref "D3") (pin "3") (pinfunction "3_3") (pintype "input"))
    )
    (net (code "157") (name "USB2P") (class "Default")
      (node (ref "D3") (pin "1") (pinfunction "1_1") (pintype "input"))
    )
    (net (code "158") (name "USB3DN1") (class "Default")
      (node (ref "D6") (pin "6") (pinfunction "6_6") (pintype "input"))
      (node (ref "U10") (pin "41") (pinfunction "U2DP1_41") (pintype "unspecified"))
    )
    (net (code "159") (name "USB3DN2") (class "Default")
      (node (ref "D7") (pin "6") (pinfunction "6_6") (pintype "input"))
      (node (ref "U10") (pin "50") (pinfunction "U2DP2_50") (pintype "unspecified"))
    )
    (net (code "160") (name "USB3DP1") (class "Default")
      (node (ref "D6") (pin "4") (pinfunction "4_4") (pintype "input"))
      (node (ref "U10") (pin "42") (pinfunction "U2DM1_42") (pintype "unspecified"))
    )
    (net (code "161") (name "USB3DP2") (class "Default")
      (node (ref "D7") (pin "4") (pinfunction "4_4") (pintype "input"))
      (node (ref "U10") (pin "51") (pinfunction "U2DM2_51") (pintype "unspecified"))
    )
    (net (code "162") (name "USB3EN1") (class "Default")
      (node (ref "U10") (pin "27") (pinfunction "PPON1_27") (pintype "unspecified"))
      (node (ref "U13") (pin "3") (pinfunction "EN1/EN1#_3") (pintype "unspecified"))
    )
    (net (code "163") (name "USB3EN2") (class "Default")
      (node (ref "U10") (pin "25") (pinfunction "PPON2_25") (pintype "unspecified"))
      (node (ref "U13") (pin "4") (pinfunction "EN2/EN2#_4") (pintype "unspecified"))
    )
    (net (code "164") (name "USB3FLT1") (class "Default")
      (node (ref "U10") (pin "26") (pinfunction "OCI1B_26") (pintype "unspecified"))
      (node (ref "U13") (pin "8") (pinfunction "FLT1#_8") (pintype "unspecified"))
    )
    (net (code "165") (name "USB3FLT2") (class "Default")
      (node (ref "U10") (pin "24") (pinfunction "OCI2B_24") (pintype "unspecified"))
      (node (ref "U13") (pin "5") (pinfunction "FLT2#_5") (pintype "unspecified"))
    )
    (net (code "166") (name "USB3N") (class "Default")
      (node (ref "D4") (pin "3") (pinfunction "3_3") (pintype "input"))
    )
    (net (code "167") (name "USB3P") (class "Default")
      (node (ref "D4") (pin "1") (pinfunction "1_1") (pintype "input"))
    )
    (net (code "168") (name "USB3RXN1") (class "Default")
      (node (ref "D2") (pin "6") (pinfunction "6_6") (pintype "input"))
      (node (ref "U10") (pin "39") (pinfunction "U3RXDN1_39") (pintype "unspecified"))
      (node (ref "U11") (pin "5") (pinfunction "STDA_SSRX-_5") (pintype "unspecified"))
    )
    (net (code "169") (name "USB3RXN2") (class "Default")
      (node (ref "D8") (pin "6") (pinfunction "6_6") (pintype "input"))
      (node (ref "U10") (pin "48") (pinfunction "U3RXDN2_48") (pintype "unspecified"))
      (node (ref "U12") (pin "5") (pinfunction "STDA_SSRX-_5") (pintype "unspecified"))
    )
    (net (code "170") (name "USB3RXP1") (class "Default")
      (node (ref "D2") (pin "4") (pinfunction "4_4") (pintype "input"))
      (node (ref "U10") (pin "38") (pinfunction "U3RXDP1_38") (pintype "unspecified"))
      (node (ref "U11") (pin "6") (pinfunction "STDA_SSRX+_6") (pintype "unspecified"))
    )
    (net (code "171") (name "USB3RXP2") (class "Default")
      (node (ref "D8") (pin "4") (pinfunction "4_4") (pintype "input"))
      (node (ref "U10") (pin "47") (pinfunction "U3RXDP2_47") (pintype "unspecified"))
      (node (ref "U12") (pin "6") (pinfunction "STDA_SSRX+_6") (pintype "unspecified"))
    )
    (net (code "172") (name "USB3TXN1") (class "Default")
      (node (ref "C105") (pin "2") (pinfunction "2_2") (pintype "unspecified"))
      (node (ref "D2") (pin "3") (pinfunction "3_3") (pintype "input"))
      (node (ref "U11") (pin "8") (pinfunction "STDA_SSTX-_8") (pintype "unspecified"))
    )
    (net (code "173") (name "USB3TXN2") (class "Default")
      (node (ref "C108") (pin "2") (pinfunction "2_2") (pintype "unspecified"))
      (node (ref "D8") (pin "3") (pinfunction "3_3") (pintype "input"))
      (node (ref "U12") (pin "8") (pinfunction "STDA_SSTX-_8") (pintype "unspecified"))
    )
    (net (code "174") (name "USB3TXP1") (class "Default")
      (node (ref "C106") (pin "2") (pinfunction "2_2") (pintype "unspecified"))
      (node (ref "D2") (pin "1") (pinfunction "1_1") (pintype "input"))
      (node (ref "U11") (pin "9") (pinfunction "STDA_SSTX+_9") (pintype "unspecified"))
    )
    (net (code "175") (name "USB3TXP2") (class "Default")
      (node (ref "C107") (pin "2") (pinfunction "2_2") (pintype "unspecified"))
      (node (ref "D8") (pin "1") (pinfunction "1_1") (pintype "input"))
      (node (ref "U12") (pin "9") (pinfunction "STDA_SSTX+_9") (pintype "unspecified"))
    )
    (net (code "176") (name "USB3_CLK_N") (class "Default")
      (node (ref "U10") (pin "5") (pinfunction "PECLKN_5") (pintype "unspecified"))
    )
    (net (code "177") (name "USB3_CLK_P") (class "Default")
      (node (ref "U10") (pin "4") (pinfunction "PECLKP_4") (pintype "unspecified"))
    )
    (net (code "178") (name "USB3_CLK_REQ") (class "Default")
      (node (ref "U10") (pin "13") (pinfunction "PECREQB_13") (pintype "unspecified"))
    )
    (net (code "179") (name "USB3_RST") (class "Default")
      (node (ref "U10") (pin "2") (pinfunction "PERSTB_2") (pintype "unspecified"))
    )
    (net (code "180") (name "USB3_RX_N") (class "Default")
      (node (ref "C84") (pin "1") (pinfunction "1_1") (pintype "unspecified"))
    )
    (net (code "181") (name "USB3_RX_P") (class "Default")
      (node (ref "C83") (pin "1") (pinfunction "1_1") (pintype "unspecified"))
    )
    (net (code "182") (name "USB3_TX_N") (class "Default")
      (node (ref "U10") (pin "11") (pinfunction "PERXN_11") (pintype "unspecified"))
    )
    (net (code "183") (name "USB3_TX_P") (class "Default")
      (node (ref "U10") (pin "10") (pinfunction "PERXP_10") (pintype "unspecified"))
    )
    (net (code "184") (name "USB3_WAKE#") (class "Default")
      (node (ref "U10") (pin "3") (pinfunction "PEWAKEB_3") (pintype "unspecified"))
    )
    (net (code "185") (name "USB4N") (class "Default")
      (node (ref "D5") (pin "3") (pinfunction "3_3") (pintype "input"))
    )
    (net (code "186") (name "USB4P") (class "Default")
      (node (ref "D5") (pin "1") (pinfunction "1_1") (pintype "input"))
    )
    (net (code "187") (name "USB_VBUS_P1") (class "Default")
      (node (ref "C75") (pin "2") (pinfunction "2_2") (pintype "unspecified"))
      (node (ref "C79") (pin "2") (pinfunction "2_2") (pintype "unspecified"))
      (node (ref "D1") (pin "5") (pinfunction "5_5") (pintype "input"))
      (node (ref "U14") (pin "7") (pinfunction "OUT1_7") (pintype "output"))
      (node (ref "USB1") (pin "1") (pinfunction "VBUS_1") (pintype "unspecified"))
    )
    (net (code "188") (name "USB_VBUS_P2") (class "Default")
      (node (ref "C76") (pin "2") (pinfunction "2_2") (pintype "unspecified"))
      (node (ref "C80") (pin "2") (pinfunction "2_2") (pintype "unspecified"))
      (node (ref "D3") (pin "5") (pinfunction "5_5") (pintype "input"))
      (node (ref "U14") (pin "6") (pinfunction "OUT2_6") (pintype "output"))
      (node (ref "USB1") (pin "5") (pinfunction "VBUS_5") (pintype "unspecified"))
    )
    (net (code "189") (name "USB_VBUS_P3") (class "Default")
      (node (ref "C77") (pin "1") (pinfunction "1_1") (pintype "unspecified"))
      (node (ref "C81") (pin "2") (pinfunction "2_2") (pintype "unspecified"))
      (node (ref "D4") (pin "5") (pinfunction "5_5") (pintype "input"))
      (node (ref "U15") (pin "7") (pinfunction "OUT1_7") (pintype "output"))
      (node (ref "USB2") (pin "1") (pinfunction "VBUS_1") (pintype "unspecified"))
    )
    (net (code "190") (name "USB_VBUS_P4") (class "Default")
      (node (ref "C78") (pin "2") (pinfunction "2_2") (pintype "unspecified"))
      (node (ref "C82") (pin "2") (pinfunction "2_2") (pintype "unspecified"))
      (node (ref "D5") (pin "5") (pinfunction "5_5") (pintype "input"))
      (node (ref "U15") (pin "6") (pinfunction "OUT2_6") (pintype "output"))
      (node (ref "USB2") (pin "5") (pinfunction "VBUS_5") (pintype "unspecified"))
    )
    (net (code "191") (name "VCC_ETH") (class "Default")
      (node (ref "C52") (pin "2") (pinfunction "2_2") (pintype "unspecified"))
      (node (ref "C53") (pin "1") (pinfunction "1_1") (pintype "unspecified"))
      (node (ref "C54") (pin "2") (pinfunction "2_2") (pintype "unspecified"))
      (node (ref "C55") (pin "2") (pinfunction "2_2") (pintype "unspecified"))
      (node (ref "C60") (pin "2") (pinfunction "2_2") (pintype "unspecified"))
      (node (ref "C62") (pin "2") (pinfunction "2_2") (pintype "unspecified"))
      (node (ref "C65") (pin "1") (pinfunction "1_1") (pintype "unspecified"))
      (node (ref "C66") (pin "1") (pinfunction "1_1") (pintype "unspecified"))
      (node (ref "C68") (pin "1") (pinfunction "1_1") (pintype "unspecified"))
      (node (ref "C69") (pin "1") (pinfunction "1_1") (pintype "unspecified"))
      (node (ref "C70") (pin "1") (pinfunction "1_1") (pintype "unspecified"))
      (node (ref "L2") (pin "1") (pinfunction "1_1") (pintype "unspecified"))
      (node (ref "R10") (pin "1") (pinfunction "1_1") (pintype "input"))
      (node (ref "R17") (pin "2") (pinfunction "2_2") (pintype "input"))
      (node (ref "R18") (pin "2") (pinfunction "2_2") (pintype "input"))
      (node (ref "R19") (pin "1") (pinfunction "1_1") (pintype "unspecified"))
      (node (ref "R22") (pin "2") (pinfunction "2_2") (pintype "input"))
      (node (ref "RJ1") (pin "L2") (pinfunction "LED_G+O-_L2") (pintype "unspecified"))
      (node (ref "RJ1") (pin "L4") (pinfunction "LED_Y+_L4") (pintype "unspecified"))
      (node (ref "RJ1") (pin "R5") (pinfunction "CT_R5") (pintype "unspecified"))
      (node (ref "RJ1") (pin "R6") (pinfunction "CT_R6") (pintype "unspecified"))
      (node (ref "U8") (pin "15") (pinfunction "AVDD33_15") (pintype "unspecified"))
      (node (ref "U8") (pin "19") (pinfunction "AVDD33_19") (pintype "unspecified"))
      (node (ref "U8") (pin "29") (pinfunction "DVDD33_29") (pintype "unspecified"))
      (node (ref "U8") (pin "33") (pinfunction "AVDD33_33") (pintype "unspecified"))
      (node (ref "U8") (pin "34") (pinfunction "AVDD33_XTAL_34") (pintype "unspecified"))
      (node (ref "U8") (pin "43") (pinfunction "EVDD33_43") (pintype "unspecified"))
      (node (ref "U8") (pin "46") (pinfunction "DVDD33_46") (pintype "unspecified"))
      (node (ref "X1") (pin "1") (pinfunction "ENABLE_CONTROL_1") (pintype "unspecified"))
      (node (ref "X1") (pin "4") (pinfunction "VDD_4") (pintype "unspecified"))
    )
    (net (code "192") (name "WIFI_CLKREQ_N") (class "Default")
      (node (ref "R12") (pin "2") (pinfunction "2_2") (pintype "unspecified"))
      (node (ref "U6") (pin "53") (pinfunction "53_53") (pintype "unspecified"))
    )
    (net (code "193") (name "WIFI_CLK_N") (class "Default")
      (node (ref "U6") (pin "49") (pinfunction "49_49") (pintype "unspecified"))
    )
    (net (code "194") (name "WIFI_CLK_P") (class "Default")
      (node (ref "U6") (pin "47") (pinfunction "47_47") (pintype "unspecified"))
    )
    (net (code "195") (name "WIFI_RST_N") (class "Default")
      (node (ref "C35") (pin "2") (pinfunction "2_2") (pintype "unspecified"))
      (node (ref "R9") (pin "1") (pinfunction "1_1") (pintype "unspecified"))
      (node (ref "U6") (pin "52") (pinfunction "52_52") (pintype "unspecified"))
    )
    (net (code "196") (name "WIFI_RX_N") (class "Default")
      (node (ref "U6") (pin "37") (pinfunction "37_37") (pintype "unspecified"))
    )
    (net (code "197") (name "WIFI_RX_P") (class "Default")
      (node (ref "U6") (pin "35") (pinfunction "35_35") (pintype "unspecified"))
    )
    (net (code "198") (name "WIFI_TX_N") (class "Default")
      (node (ref "C34") (pin "2") (pinfunction "2_2") (pintype "unspecified"))
    )
    (net (code "199") (name "WIFI_TX_P") (class "Default")
      (node (ref "C33") (pin "2") (pinfunction "2_2") (pintype "unspecified"))
    )
    (net (code "200") (name "WIFI_WAKE_N") (class "Default")
      (node (ref "R13") (pin "2") (pinfunction "2_2") (pintype "unspecified"))
      (node (ref "U6") (pin "55") (pinfunction "55_55") (pintype "unspecified"))
    )
    (net (code "201") (name "unconnected-(CN1-P1-Pad8)") (class "Default")
      (node (ref "CN1") (pin "8") (pinfunction "P1_8") (pintype "unspecified+no_connect"))
    )
    (net (code "202") (name "unconnected-(CN1-P2-Pad9)") (class "Default")
      (node (ref "CN1") (pin "9") (pinfunction "P2_9") (pintype "unspecified+no_connect"))
    )
    (net (code "203") (name "unconnected-(CN1-P3-Pad10)") (class "Default")
      (node (ref "CN1") (pin "10") (pinfunction "P3_10") (pintype "unspecified+no_connect"))
    )
    (net (code "204") (name "unconnected-(CN1-P5-Pad22)") (class "Default")
      (node (ref "CN1") (pin "22") (pinfunction "P5_22") (pintype "unspecified+no_connect"))
    )
    (net (code "205") (name "unconnected-(CN1-P13-Pad20)") (class "Default")
      (node (ref "CN1") (pin "20") (pinfunction "P13_20") (pintype "unspecified+no_connect"))
    )
    (net (code "206") (name "unconnected-(CN1-P14-Pad21)") (class "Default")
      (node (ref "CN1") (pin "21") (pinfunction "P14_21") (pintype "unspecified+no_connect"))
    )
    (net (code "207") (name "unconnected-(CN2-P1-Pad8)") (class "Default")
      (node (ref "CN2") (pin "8") (pinfunction "P1_8") (pintype "unspecified+no_connect"))
    )
    (net (code "208") (name "unconnected-(CN2-P2-Pad9)") (class "Default")
      (node (ref "CN2") (pin "9") (pinfunction "P2_9") (pintype "unspecified+no_connect"))
    )
    (net (code "209") (name "unconnected-(CN2-P3-Pad10)") (class "Default")
      (node (ref "CN2") (pin "10") (pinfunction "P3_10") (pintype "unspecified+no_connect"))
    )
    (net (code "210") (name "unconnected-(CN2-P5-Pad22)") (class "Default")
      (node (ref "CN2") (pin "22") (pinfunction "P5_22") (pintype "unspecified+no_connect"))
    )
    (net (code "211") (name "unconnected-(CN2-P13-Pad20)") (class "Default")
      (node (ref "CN2") (pin "20") (pinfunction "P13_20") (pintype "unspecified+no_connect"))
    )
    (net (code "212") (name "unconnected-(CN2-P14-Pad21)") (class "Default")
      (node (ref "CN2") (pin "21") (pinfunction "P14_21") (pintype "unspecified+no_connect"))
    )
    (net (code "213") (name "unconnected-(U6-Pad6)") (class "Default")
      (node (ref "U6") (pin "6") (pinfunction "6_6") (pintype "unspecified+no_connect"))
    )
    (net (code "214") (name "unconnected-(U6-Pad8)") (class "Default")
      (node (ref "U6") (pin "8") (pinfunction "8_8") (pintype "unspecified+no_connect"))
    )
    (net (code "215") (name "unconnected-(U6-Pad9)") (class "Default")
      (node (ref "U6") (pin "9") (pinfunction "9_9") (pintype "unspecified+no_connect"))
    )
    (net (code "216") (name "unconnected-(U6-Pad10)") (class "Default")
      (node (ref "U6") (pin "10") (pinfunction "10_10") (pintype "unspecified+no_connect"))
    )
    (net (code "217") (name "unconnected-(U6-Pad11)") (class "Default")
      (node (ref "U6") (pin "11") (pinfunction "11_11") (pintype "unspecified+no_connect"))
    )
    (net (code "218") (name "unconnected-(U6-Pad12)") (class "Default")
      (node (ref "U6") (pin "12") (pinfunction "12_12") (pintype "unspecified+no_connect"))
    )
    (net (code "219") (name "unconnected-(U6-Pad13)") (class "Default")
      (node (ref "U6") (pin "13") (pinfunction "13_13") (pintype "unspecified+no_connect"))
    )
    (net (code "220") (name "unconnected-(U6-Pad14)") (class "Default")
      (node (ref "U6") (pin "14") (pinfunction "14_14") (pintype "unspecified+no_connect"))
    )
    (net (code "221") (name "unconnected-(U6-Pad15)") (class "Default")
      (node (ref "U6") (pin "15") (pinfunction "15_15") (pintype "unspecified+no_connect"))
    )
    (net (code "222") (name "unconnected-(U6-Pad16)") (class "Default")
      (node (ref "U6") (pin "16") (pinfunction "16_16") (pintype "unspecified+no_connect"))
    )
    (net (code "223") (name "unconnected-(U6-Pad17)") (class "Default")
      (node (ref "U6") (pin "17") (pinfunction "17_17") (pintype "unspecified+no_connect"))
    )
    (net (code "224") (name "unconnected-(U6-Pad18)") (class "Default")
      (node (ref "U6") (pin "18") (pinfunction "18_18") (pintype "unspecified+no_connect"))
    )
    (net (code "225") (name "unconnected-(U6-Pad19)") (class "Default")
      (node (ref "U6") (pin "19") (pinfunction "19_19") (pintype "unspecified+no_connect"))
    )
    (net (code "226") (name "unconnected-(U6-Pad20)") (class "Default")
      (node (ref "U6") (pin "20") (pinfunction "20_20") (pintype "unspecified+no_connect"))
    )
    (net (code "227") (name "unconnected-(U6-Pad21)") (class "Default")
      (node (ref "U6") (pin "21") (pinfunction "21_21") (pintype "unspecified+no_connect"))
    )
    (net (code "228") (name "unconnected-(U6-Pad22)") (class "Default")
      (node (ref "U6") (pin "22") (pinfunction "22_22") (pintype "unspecified+no_connect"))
    )
    (net (code "229") (name "unconnected-(U6-Pad23)") (class "Default")
      (node (ref "U6") (pin "23") (pinfunction "23_23") (pintype "unspecified+no_connect"))
    )
    (net (code "230") (name "unconnected-(U6-Pad32)") (class "Default")
      (node (ref "U6") (pin "32") (pinfunction "32_32") (pintype "unspecified+no_connect"))
    )
    (net (code "231") (name "unconnected-(U6-Pad34)") (class "Default")
      (node (ref "U6") (pin "34") (pinfunction "34_34") (pintype "unspecified+no_connect"))
    )
    (net (code "232") (name "unconnected-(U6-Pad36)") (class "Default")
      (node (ref "U6") (pin "36") (pinfunction "36_36") (pintype "unspecified+no_connect"))
    )
    (net (code "233") (name "unconnected-(U6-Pad38)") (class "Default")
      (node (ref "U6") (pin "38") (pinfunction "38_38") (pintype "unspecified+no_connect"))
    )
    (net (code "234") (name "unconnected-(U6-Pad40)") (class "Default")
      (node (ref "U6") (pin "40") (pinfunction "40_40") (pintype "unspecified+no_connect"))
    )
    (net (code "235") (name "unconnected-(U6-Pad42)") (class "Default")
      (node (ref "U6") (pin "42") (pinfunction "42_42") (pintype "unspecified+no_connect"))
    )
    (net (code "236") (name "unconnected-(U6-Pad44)") (class "Default")
      (node (ref "U6") (pin "44") (pinfunction "44_44") (pintype "unspecified+no_connect"))
    )
    (net (code "237") (name "unconnected-(U6-Pad46)") (class "Default")
      (node (ref "U6") (pin "46") (pinfunction "46_46") (pintype "unspecified+no_connect"))
    )
    (net (code "238") (name "unconnected-(U6-Pad48)") (class "Default")
      (node (ref "U6") (pin "48") (pinfunction "48_48") (pintype "unspecified+no_connect"))
    )
    (net (code "239") (name "unconnected-(U6-Pad50)") (class "Default")
      (node (ref "U6") (pin "50") (pinfunction "50_50") (pintype "unspecified+no_connect"))
    )
    (net (code "240") (name "unconnected-(U6-Pad54)") (class "Default")
      (node (ref "U6") (pin "54") (pinfunction "54_54") (pintype "unspecified+no_connect"))
    )
    (net (code "241") (name "unconnected-(U6-Pad56)") (class "Default")
      (node (ref "U6") (pin "56") (pinfunction "56_56") (pintype "unspecified+no_connect"))
    )
    (net (code "242") (name "unconnected-(U6-Pad58)") (class "Default")
      (node (ref "U6") (pin "58") (pinfunction "58_58") (pintype "unspecified+no_connect"))
    )
    (net (code "243") (name "unconnected-(U6-Pad59)") (class "Default")
      (node (ref "U6") (pin "59") (pinfunction "59_59") (pintype "unspecified+no_connect"))
    )
    (net (code "244") (name "unconnected-(U6-Pad60)") (class "Default")
      (node (ref "U6") (pin "60") (pinfunction "60_60") (pintype "unspecified+no_connect"))
    )
    (net (code "245") (name "unconnected-(U6-Pad61)") (class "Default")
      (node (ref "U6") (pin "61") (pinfunction "61_61") (pintype "unspecified+no_connect"))
    )
    (net (code "246") (name "unconnected-(U6-Pad62)") (class "Default")
      (node (ref "U6") (pin "62") (pinfunction "62_62") (pintype "unspecified+no_connect"))
    )
    (net (code "247") (name "unconnected-(U6-Pad64)") (class "Default")
      (node (ref "U6") (pin "64") (pinfunction "64_64") (pintype "unspecified+no_connect"))
    )
    (net (code "248") (name "unconnected-(U6-Pad65)") (class "Default")
      (node (ref "U6") (pin "65") (pinfunction "65_65") (pintype "unspecified+no_connect"))
    )
    (net (code "249") (name "unconnected-(U6-Pad66)") (class "Default")
      (node (ref "U6") (pin "66") (pinfunction "66_66") (pintype "unspecified+no_connect"))
    )
    (net (code "250") (name "unconnected-(U6-Pad67)") (class "Default")
      (node (ref "U6") (pin "67") (pinfunction "67_67") (pintype "unspecified+no_connect"))
    )
    (net (code "251") (name "unconnected-(U6-Pad68)") (class "Default")
      (node (ref "U6") (pin "68") (pinfunction "68_68") (pintype "unspecified+no_connect"))
    )
    (net (code "252") (name "unconnected-(U6-Pad70)") (class "Default")
      (node (ref "U6") (pin "70") (pinfunction "70_70") (pintype "unspecified+no_connect"))
    )
    (net (code "253") (name "unconnected-(U6-Pad71)") (class "Default")
      (node (ref "U6") (pin "71") (pinfunction "71_71") (pintype "unspecified+no_connect"))
    )
    (net (code "254") (name "unconnected-(U6-Pad73)") (class "Default")
      (node (ref "U6") (pin "73") (pinfunction "73_73") (pintype "unspecified+no_connect"))
    )
    (net (code "255") (name "unconnected-(U7-Pad6)") (class "Default")
      (node (ref "U7") (pin "6") (pinfunction "6_6") (pintype "unspecified+no_connect"))
    )
    (net (code "256") (name "unconnected-(U7-Pad8)") (class "Default")
      (node (ref "U7") (pin "8") (pinfunction "8_8") (pintype "unspecified+no_connect"))
    )
    (net (code "257") (name "unconnected-(U7-Pad10)") (class "Default")
      (node (ref "U7") (pin "10") (pinfunction "10_10") (pintype "unspecified+no_connect"))
    )
    (net (code "258") (name "unconnected-(U7-Pad12)") (class "Default")
      (node (ref "U7") (pin "12") (pinfunction "12_12") (pintype "unspecified+no_connect"))
    )
    (net (code "259") (name "unconnected-(U7-Pad14)") (class "Default")
      (node (ref "U7") (pin "14") (pinfunction "14_14") (pintype "unspecified+no_connect"))
    )
    (net (code "260") (name "unconnected-(U7-Pad16)") (class "Default")
      (node (ref "U7") (pin "16") (pinfunction "16_16") (pintype "unspecified+no_connect"))
    )
    (net (code "261") (name "unconnected-(U7-Pad18)") (class "Default")
      (node (ref "U7") (pin "18") (pinfunction "18_18") (pintype "unspecified+no_connect"))
    )
    (net (code "262") (name "unconnected-(U7-Pad20)") (class "Default")
      (node (ref "U7") (pin "20") (pinfunction "20_20") (pintype "unspecified+no_connect"))
    )
    (net (code "263") (name "unconnected-(U7-Pad22)") (class "Default")
      (node (ref "U7") (pin "22") (pinfunction "22_22") (pintype "unspecified+no_connect"))
    )
    (net (code "264") (name "unconnected-(U7-Pad24)") (class "Default")
      (node (ref "U7") (pin "24") (pinfunction "24_24") (pintype "unspecified+no_connect"))
    )
    (net (code "265") (name "unconnected-(U7-Pad26)") (class "Default")
      (node (ref "U7") (pin "26") (pinfunction "26_26") (pintype "unspecified+no_connect"))
    )
    (net (code "266") (name "unconnected-(U7-Pad28)") (class "Default")
      (node (ref "U7") (pin "28") (pinfunction "28_28") (pintype "unspecified+no_connect"))
    )
    (net (code "267") (name "unconnected-(U7-Pad30)") (class "Default")
      (node (ref "U7") (pin "30") (pinfunction "30_30") (pintype "unspecified+no_connect"))
    )
    (net (code "268") (name "unconnected-(U7-Pad32)") (class "Default")
      (node (ref "U7") (pin "32") (pinfunction "32_32") (pintype "unspecified+no_connect"))
    )
    (net (code "269") (name "unconnected-(U7-Pad34)") (class "Default")
      (node (ref "U7") (pin "34") (pinfunction "34_34") (pintype "unspecified+no_connect"))
    )
    (net (code "270") (name "unconnected-(U7-Pad36)") (class "Default")
      (node (ref "U7") (pin "36") (pinfunction "36_36") (pintype "unspecified+no_connect"))
    )
    (net (code "271") (name "unconnected-(U7-Pad38)") (class "Default")
      (node (ref "U7") (pin "38") (pinfunction "38_38") (pintype "unspecified+no_connect"))
    )
    (net (code "272") (name "unconnected-(U7-Pad40)") (class "Default")
      (node (ref "U7") (pin "40") (pinfunction "40_40") (pintype "unspecified+no_connect"))
    )
    (net (code "273") (name "unconnected-(U7-Pad42)") (class "Default")
      (node (ref "U7") (pin "42") (pinfunction "42_42") (pintype "unspecified+no_connect"))
    )
    (net (code "274") (name "unconnected-(U7-Pad44)") (class "Default")
      (node (ref "U7") (pin "44") (pinfunction "44_44") (pintype "unspecified+no_connect"))
    )
    (net (code "275") (name "unconnected-(U7-Pad46)") (class "Default")
      (node (ref "U7") (pin "46") (pinfunction "46_46") (pintype "unspecified+no_connect"))
    )
    (net (code "276") (name "unconnected-(U7-Pad48)") (class "Default")
      (node (ref "U7") (pin "48") (pinfunction "48_48") (pintype "unspecified+no_connect"))
    )
    (net (code "277") (name "unconnected-(U7-Pad56)") (class "Default")
      (node (ref "U7") (pin "56") (pinfunction "56_56") (pintype "unspecified+no_connect"))
    )
    (net (code "278") (name "unconnected-(U7-Pad58)") (class "Default")
      (node (ref "U7") (pin "58") (pinfunction "58_58") (pintype "unspecified+no_connect"))
    )
    (net (code "279") (name "unconnected-(U7-Pad67)") (class "Default")
      (node (ref "U7") (pin "67") (pinfunction "67_67") (pintype "unspecified+no_connect"))
    )
    (net (code "280") (name "unconnected-(U7-Pad68)") (class "Default")
      (node (ref "U7") (pin "68") (pinfunction "68_68") (pintype "unspecified+no_connect"))
    )
    (net (code "281") (name "unconnected-(U7-Pad69)") (class "Default")
      (node (ref "U7") (pin "69") (pinfunction "69_69") (pintype "unspecified+no_connect"))
    )
    (net (code "282") (name "unconnected-(U8-CKXTAL2-Pad9)") (class "Default")
      (node (ref "U8") (pin "9") (pinfunction "CKXTAL2_9") (pintype "unspecified+no_connect"))
    )
    (net (code "283") (name "unconnected-(U8-EECS{slash}SCL-Pad31)") (class "Default")
      (node (ref "U8") (pin "31") (pinfunction "EECS/SCL_31") (pintype "unspecified+no_connect"))
    )
    (net (code "284") (name "unconnected-(U8-EEPROM_SEL{slash}PPS_PIN-Pad32)") (class "Default")
      (node (ref "U8") (pin "32") (pinfunction "EEPROM_SEL/PPS_PIN_32") (pintype "unspecified+no_connect"))
    )
    (net (code "285") (name "unconnected-(U8-GPI-Pad3)") (class "Default")
      (node (ref "U8") (pin "3") (pinfunction "GPI_3") (pintype "unspecified+no_connect"))
    )
    (net (code "286") (name "unconnected-(U8-LED3-Pad35)") (class "Default")
      (node (ref "U8") (pin "35") (pinfunction "LED3_35") (pintype "unspecified+no_connect"))
    )
    (net (code "287") (name "unconnected-(U8-NC-Pad4)") (class "Default")
      (node (ref "U8") (pin "4") (pinfunction "NC_4") (pintype "unspecified+no_connect"))
    )
    (net (code "288") (name "unconnected-(U8-NC-Pad5)") (class "Default")
      (node (ref "U8") (pin "5") (pinfunction "NC_5") (pintype "unspecified+no_connect"))
    )
    (net (code "289") (name "unconnected-(U8-NC-Pad7)") (class "Default")
      (node (ref "U8") (pin "7") (pinfunction "NC_7") (pintype "unspecified+no_connect"))
    )
    (net (code "290") (name "unconnected-(U8-SPICSB-Pad26)") (class "Default")
      (node (ref "U8") (pin "26") (pinfunction "SPICSB_26") (pintype "unspecified+no_connect"))
    )
    (net (code "291") (name "unconnected-(U9-NC{slash}PG-Pad6)") (class "Default")
      (node (ref "U9") (pin "6") (pinfunction "NC/PG_6") (pintype "unspecified+no_connect"))
    )
    (net (code "292") (name "unconnected-(U10-OCI3B-Pad22)") (class "Default")
      (node (ref "U10") (pin "22") (pinfunction "OCI3B_22") (pintype "unspecified+no_connect"))
    )
    (net (code "293") (name "unconnected-(U10-OCI4B-Pad20)") (class "Default")
      (node (ref "U10") (pin "20") (pinfunction "OCI4B_20") (pintype "unspecified+no_connect"))
    )
    (net (code "294") (name "unconnected-(U10-PPON3-Pad23)") (class "Default")
      (node (ref "U10") (pin "23") (pinfunction "PPON3_23") (pintype "unspecified+no_connect"))
    )
    (net (code "295") (name "unconnected-(U10-PPON4-Pad21)") (class "Default")
      (node (ref "U10") (pin "21") (pinfunction "PPON4_21") (pintype "unspecified+no_connect"))
    )
    (net (code "296") (name "unconnected-(U10-U2DM3-Pad59)") (class "Default")
      (node (ref "U10") (pin "59") (pinfunction "U2DM3_59") (pintype "unspecified+no_connect"))
    )
    (net (code "297") (name "unconnected-(U10-U2DM4-Pad68)") (class "Default")
      (node (ref "U10") (pin "68") (pinfunction "U2DM4_68") (pintype "unspecified+no_connect"))
    )
    (net (code "298") (name "unconnected-(U10-U2DP3-Pad58)") (class "Default")
      (node (ref "U10") (pin "58") (pinfunction "U2DP3_58") (pintype "unspecified+no_connect"))
    )
    (net (code "299") (name "unconnected-(U10-U2DP4-Pad67)") (class "Default")
      (node (ref "U10") (pin "67") (pinfunction "U2DP4_67") (pintype "unspecified+no_connect"))
    )
    (net (code "300") (name "unconnected-(U10-U3RXDN3-Pad56)") (class "Default")
      (node (ref "U10") (pin "56") (pinfunction "U3RXDN3_56") (pintype "unspecified+no_connect"))
    )
    (net (code "301") (name "unconnected-(U10-U3RXDN4-Pad65)") (class "Default")
      (node (ref "U10") (pin "65") (pinfunction "U3RXDN4_65") (pintype "unspecified+no_connect"))
    )
    (net (code "302") (name "unconnected-(U10-U3RXDP3-Pad55)") (class "Default")
      (node (ref "U10") (pin "55") (pinfunction "U3RXDP3_55") (pintype "unspecified+no_connect"))
    )
    (net (code "303") (name "unconnected-(U10-U3RXDP4-Pad64)") (class "Default")
      (node (ref "U10") (pin "64") (pinfunction "U3RXDP4_64") (pintype "unspecified+no_connect"))
    )
    (net (code "304") (name "unconnected-(U10-U3TXDN3-Pad53)") (class "Default")
      (node (ref "U10") (pin "53") (pinfunction "U3TXDN3_53") (pintype "unspecified+no_connect"))
    )
    (net (code "305") (name "unconnected-(U10-U3TXDN4-Pad62)") (class "Default")
      (node (ref "U10") (pin "62") (pinfunction "U3TXDN4_62") (pintype "unspecified+no_connect"))
    )
    (net (code "306") (name "unconnected-(U10-U3TXDP3-Pad52)") (class "Default")
      (node (ref "U10") (pin "52") (pinfunction "U3TXDP3_52") (pintype "unspecified+no_connect"))
    )
    (net (code "307") (name "unconnected-(U10-U3TXDP4-Pad61)") (class "Default")
      (node (ref "U10") (pin "61") (pinfunction "U3TXDP4_61") (pintype "unspecified+no_connect"))
    )
  )
)
